# AT_SoM_Carrier_Board_V0_3r2.net
KiCad netlist of a schematic drawn in EAGLE
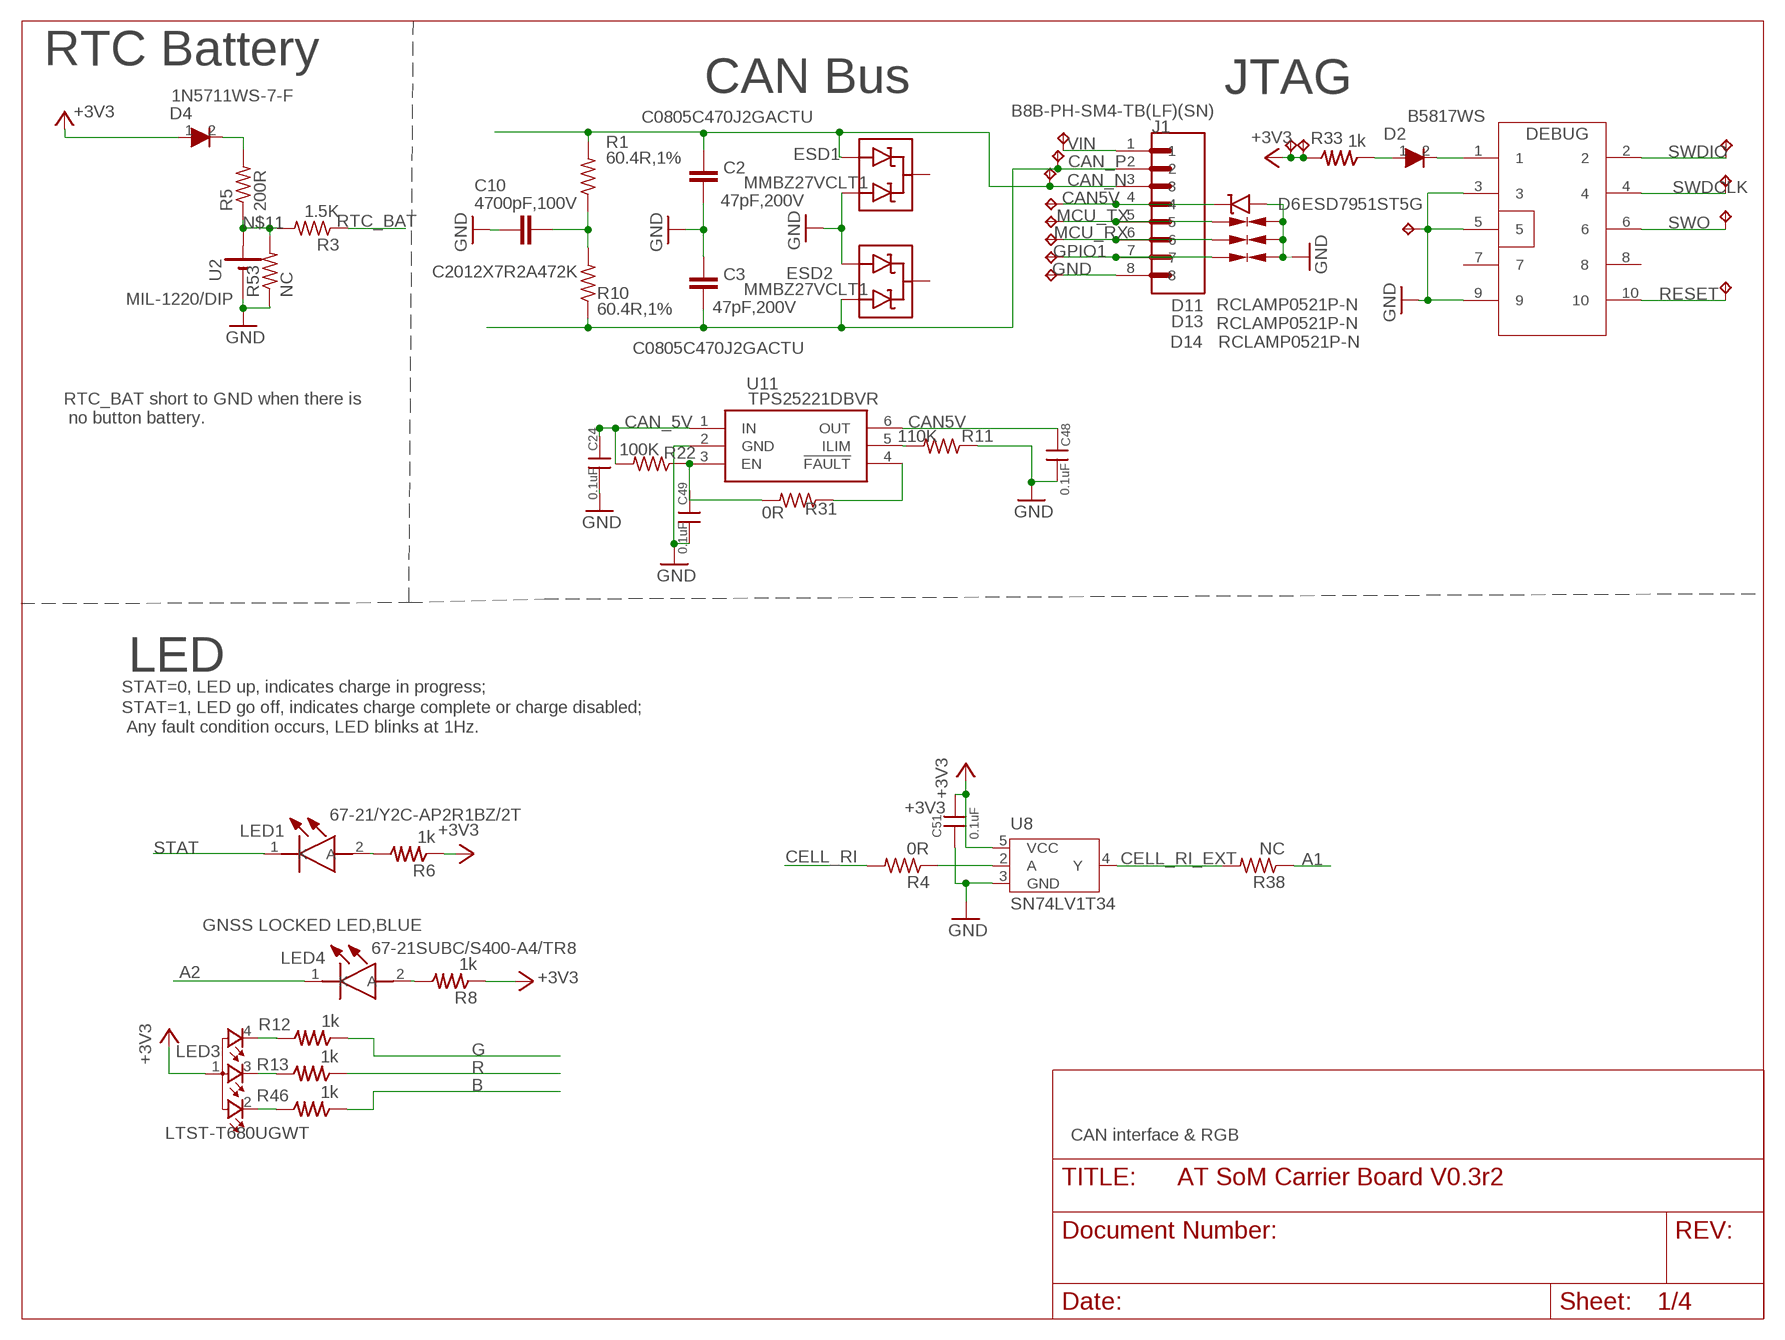
[diagram p0: schematic, sheet 1]
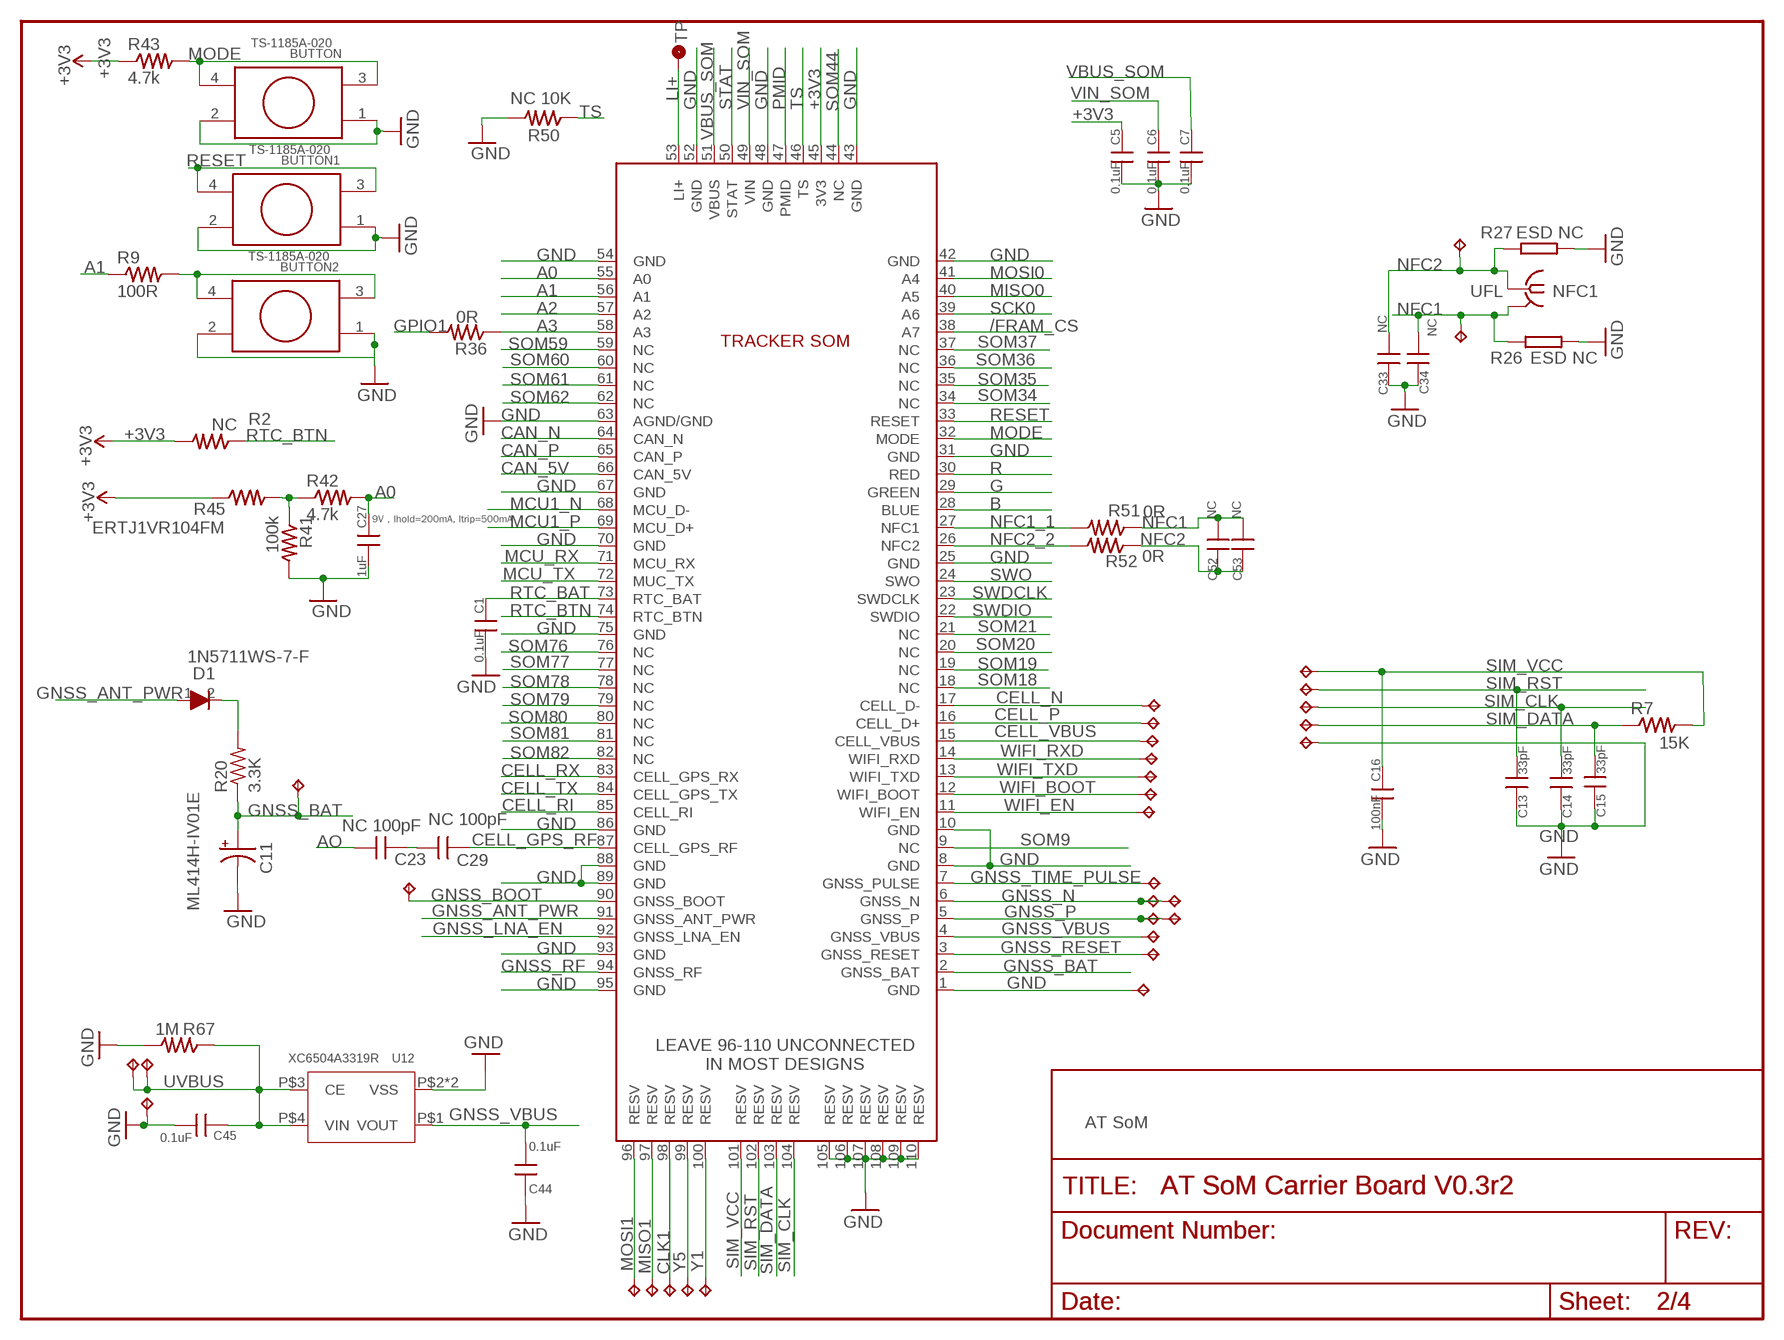
[diagram p1: schematic, sheet 2]
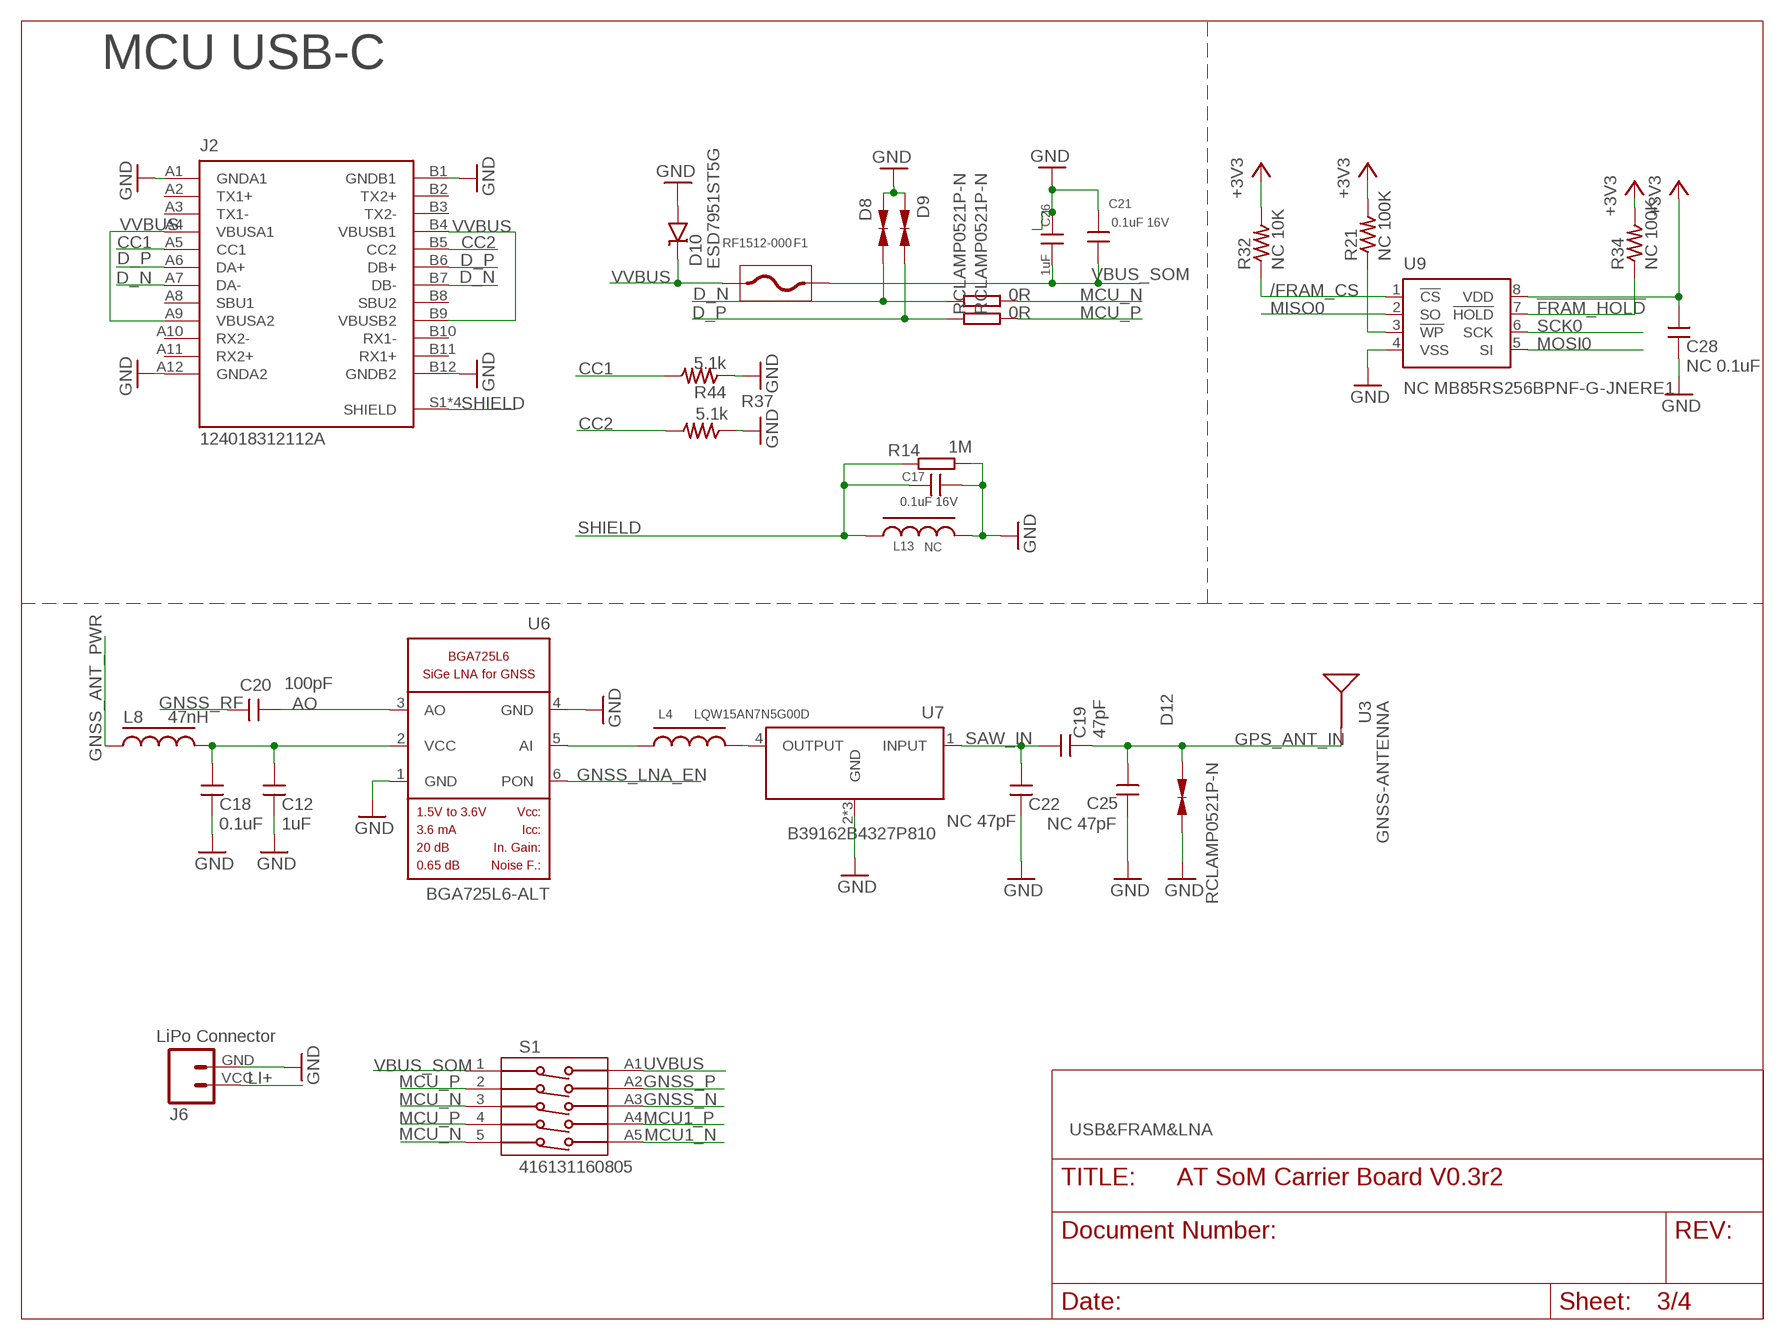
[diagram p2: schematic, sheet 3]
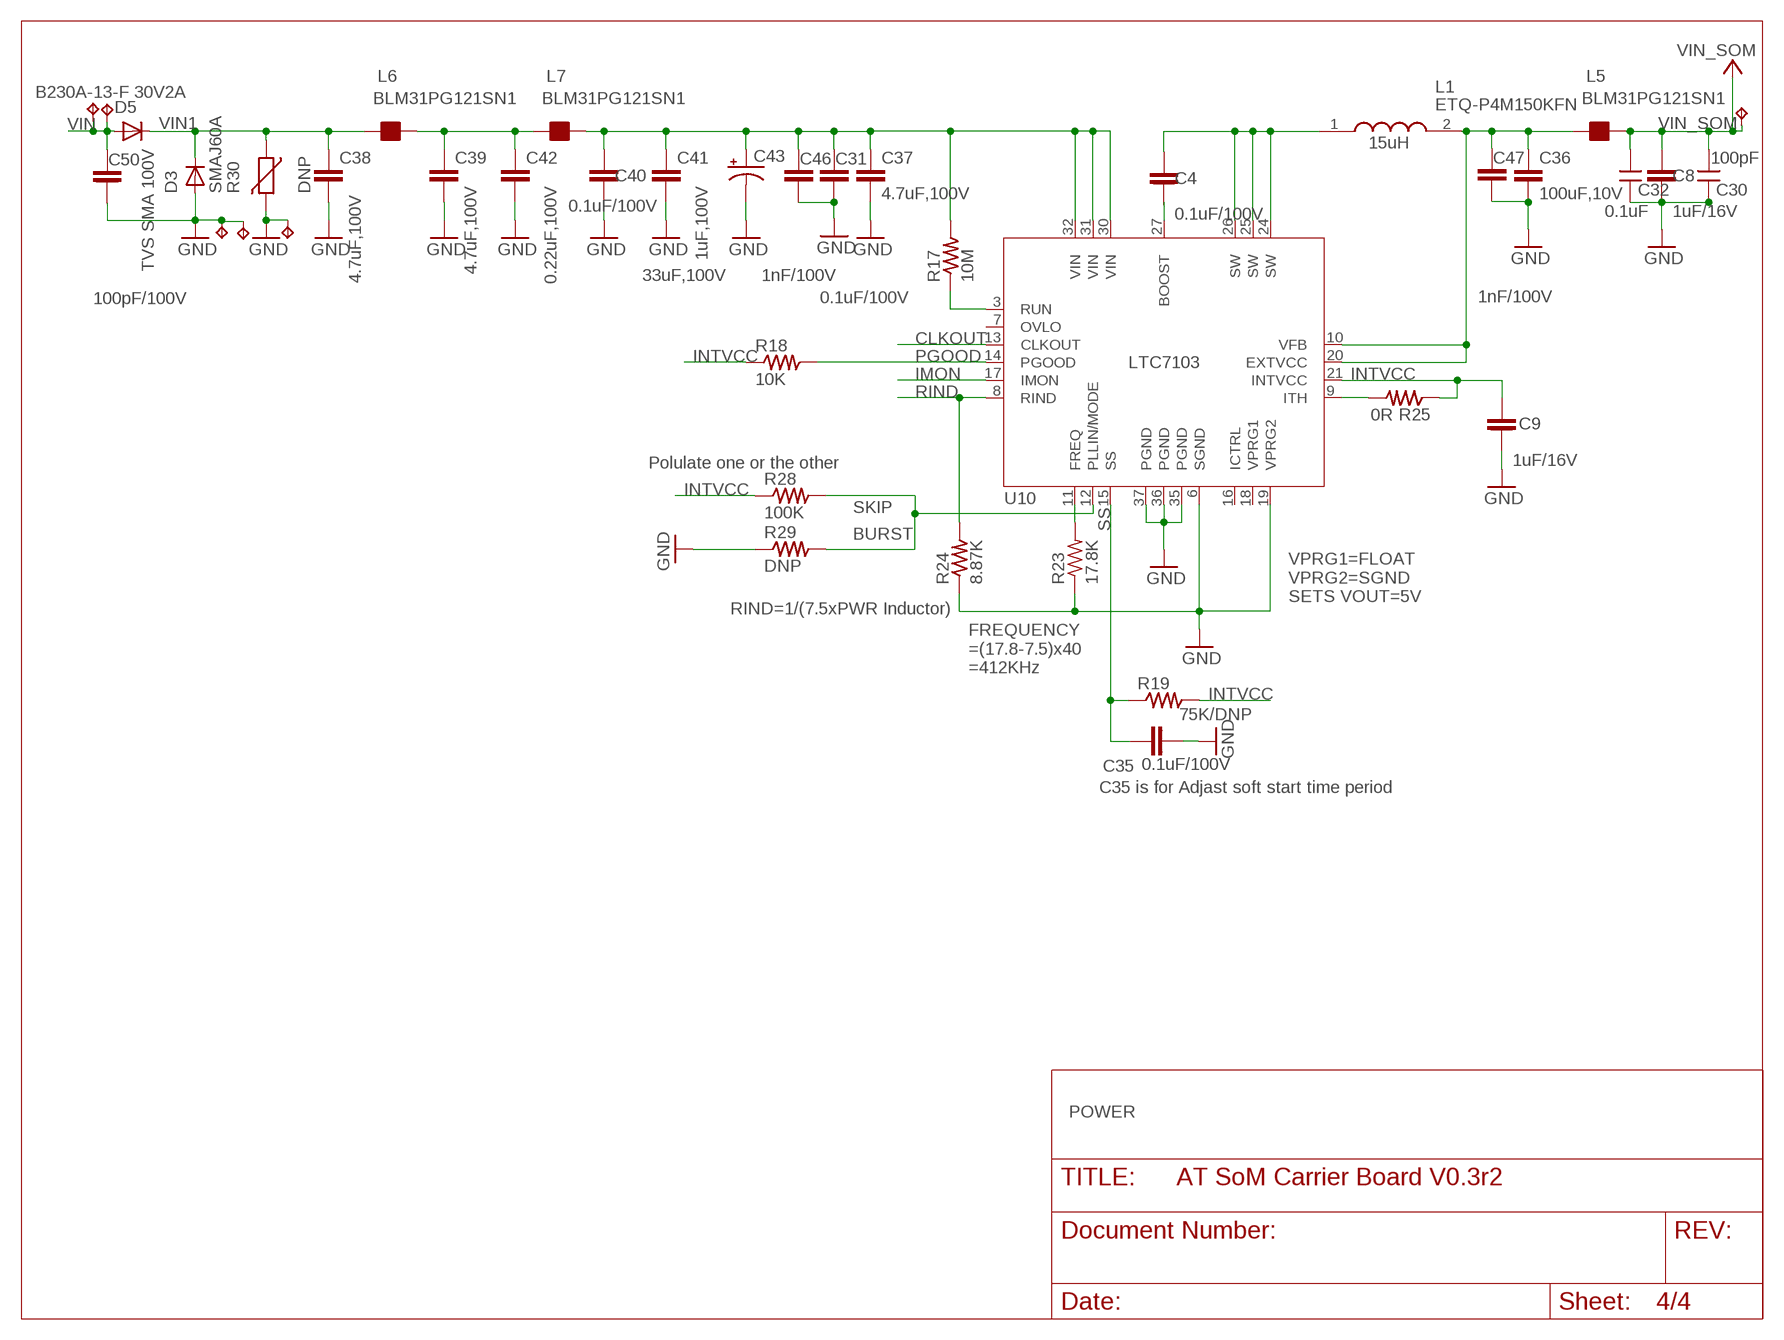
[diagram p3: schematic, sheet 4]

(export (version "E")
  (design (tool "Eeschema 10.0.6"))
  (components
    (comp (ref "C4")
      (value "0.1uF/100V")
      (footprint "eagle-import:C-0603A")
      (libsource (lib "eagle-import") (part "CAP0603A"))
    )
    (comp (ref "C8")
      (value "1uF/16V")
      (footprint "eagle-import:C-0402")
      (libsource (lib "eagle-import") (part "CAP0402"))
    )
    (comp (ref "C9")
      (value "1uF/16V")
      (footprint "eagle-import:C-0402")
      (libsource (lib "eagle-import") (part "CAP0402"))
    )
    (comp (ref "C30")
      (value "100pF")
      (footprint "eagle-import:C0402_P")
      (libsource (lib "eagle-import") (part "CAP_0402"))
    )
    (comp (ref "C31")
      (value "0.1uF/100V")
      (footprint "eagle-import:C-0603A")
      (libsource (lib "eagle-import") (part "CAP0603A"))
    )
    (comp (ref "C32")
      (value "0.1uF")
      (footprint "eagle-import:C0402_P")
      (libsource (lib "eagle-import") (part "CAP_0402"))
    )
    (comp (ref "C35")
      (value "0.1uF/100V")
      (footprint "eagle-import:C-0603A")
      (libsource (lib "eagle-import") (part "CAP0603A"))
    )
    (comp (ref "C36")
      (value "100uF,10V")
      (footprint "eagle-import:C1210")
      (libsource (lib "eagle-import") (part "C-EUC1210"))
    )
    (comp (ref "C37")
      (value "4.7uF,100V")
      (footprint "eagle-import:C1210")
      (libsource (lib "eagle-import") (part "C-EUC1210"))
    )
    (comp (ref "C38")
      (value "4.7uF,100V")
      (footprint "eagle-import:C1210")
      (libsource (lib "eagle-import") (part "C-EUC1210"))
    )
    (comp (ref "C39")
      (value "4.7uF,100V")
      (footprint "eagle-import:C1210")
      (libsource (lib "eagle-import") (part "C-EUC1210"))
    )
    (comp (ref "C40")
      (value "0.1uF/100V")
      (footprint "eagle-import:C-0603A")
      (libsource (lib "eagle-import") (part "CAP0603A"))
    )
    (comp (ref "C41")
      (value "1uF,100V")
      (footprint "eagle-import:C0805")
      (libsource (lib "eagle-import") (part "C-EUC0805"))
    )
    (comp (ref "C42")
      (value "0.22uF,100V")
      (footprint "eagle-import:C0805")
      (libsource (lib "eagle-import") (part "C-EUC0805"))
    )
    (comp (ref "C43")
      (value "33uF,100V")
      (footprint "eagle-import:NIC_10X10.5_CAP")
      (libsource (lib "eagle-import") (part "100UF-POLAR-10X10.5-63V-20%"))
    )
    (comp (ref "C46")
      (value "1nF/100V")
      (footprint "eagle-import:C-0603A")
      (libsource (lib "eagle-import") (part "CAP0603A"))
    )
    (comp (ref "C47")
      (value "1nF/100V")
      (footprint "eagle-import:C-0603A")
      (libsource (lib "eagle-import") (part "CAP0603A"))
    )
    (comp (ref "C50")
      (value "100pF/100V")
      (footprint "eagle-import:C-0603A")
      (libsource (lib "eagle-import") (part "CAP0603A"))
    )
    (comp (ref "D3")
      (value "SMAJ60A")
      (footprint "eagle-import:SMADIODE")
      (libsource (lib "eagle-import") (part "DIODESMA"))
    )
    (comp (ref "D5")
      (value "B230A-13-F 30V2A")
      (footprint "eagle-import:SMADIODE")
      (libsource (lib "eagle-import") (part "DIODESMA"))
    )
    (comp (ref "L1")
      (value "ETQ-P4M150KFN")
      (footprint "eagle-import:ETQP4M150KFN")
      (libsource (lib "eagle-import") (part "ETQ-P4M150KFN"))
    )
    (comp (ref "L5")
      (value "BLM31PG121SN1")
      (footprint "eagle-import:L1206")
      (libsource (lib "eagle-import") (part "FB_1206"))
    )
    (comp (ref "L6")
      (value "BLM31PG121SN1")
      (footprint "eagle-import:L1206")
      (libsource (lib "eagle-import") (part "FB_1206"))
    )
    (comp (ref "L7")
      (value "BLM31PG121SN1")
      (footprint "eagle-import:L1206")
      (libsource (lib "eagle-import") (part "FB_1206"))
    )
    (comp (ref "R17")
      (value "10M")
      (footprint "eagle-import:R-0402S")
      (libsource (lib "eagle-import") (part "RES0402S"))
    )
    (comp (ref "R18")
      (value "10K")
      (footprint "eagle-import:R-0402S")
      (libsource (lib "eagle-import") (part "RES0402S"))
    )
    (comp (ref "R19")
      (value "75K/DNP")
      (footprint "eagle-import:R-0402S")
      (libsource (lib "eagle-import") (part "RES0402S"))
    )
    (comp (ref "R23")
      (value "17.8K")
      (footprint "eagle-import:R0603_P")
      (libsource (lib "eagle-import") (part "RES_0603"))
    )
    (comp (ref "R24")
      (value "8.87K")
      (footprint "eagle-import:R-0402S")
      (libsource (lib "eagle-import") (part "RES0402S"))
    )
    (comp (ref "R25")
      (value "0R")
      (footprint "eagle-import:R-0402S")
      (libsource (lib "eagle-import") (part "RES0402S"))
    )
    (comp (ref "R28")
      (value "100K")
      (footprint "eagle-import:R-0402S")
      (libsource (lib "eagle-import") (part "RES0402S"))
    )
    (comp (ref "R29")
      (value "DNP")
      (footprint "eagle-import:R-0402S")
      (libsource (lib "eagle-import") (part "RES0402S"))
    )
    (comp (ref "R30")
      (value "DNP")
      (footprint "eagle-import:R-5")
      (libsource (lib "eagle-import") (part "VARISTOR-2,5"))
    )
    (comp (ref "TP10")
      (value "TPTP10R")
      (footprint "eagle-import:TP10R")
      (libsource (lib "eagle-import") (part "TPTP10R"))
    )
    (comp (ref "TP23")
      (value "TPTP10R")
      (footprint "eagle-import:TP10R")
      (libsource (lib "eagle-import") (part "TPTP10R"))
    )
    (comp (ref "TP24")
      (value "TPTP10R")
      (footprint "eagle-import:TP10R")
      (libsource (lib "eagle-import") (part "TPTP10R"))
    )
    (comp (ref "TP25")
      (value "TPTP10R")
      (footprint "eagle-import:TP10R")
      (libsource (lib "eagle-import") (part "TPTP10R"))
    )
    (comp (ref "TP26")
      (value "TPTP10R")
      (footprint "eagle-import:TP10R")
      (libsource (lib "eagle-import") (part "TPTP10R"))
    )
    (comp (ref "TP45")
      (value "TPTP10R")
      (footprint "eagle-import:TP10R")
      (libsource (lib "eagle-import") (part "TPTP10R"))
    )
    (comp (ref "U10")
      (value "LTC7103")
      (footprint "eagle-import:UHE36(26)QFN")
      (libsource (lib "eagle-import") (part "LTC7103"))
    )
    (comp (ref "BUTTON")
      (value "TS-1185A-020")
      (footprint "eagle-import:TS-1185A-020")
      (libsource (lib "eagle-import") (part "TS-1185A-020"))
    )
    (comp (ref "BUTTON1")
      (value "TS-1185A-020")
      (footprint "eagle-import:TS-1185A-020")
      (libsource (lib "eagle-import") (part "TS-1185A-020"))
    )
    (comp (ref "BUTTON2")
      (value "TS-1185A-020")
      (footprint "eagle-import:TS-1185A-020")
      (libsource (lib "eagle-import") (part "TS-1185A-020"))
    )
    (comp (ref "C1")
      (value "0.1uF")
      (footprint "eagle-import:C-0402")
      (libsource (lib "eagle-import") (part "RedBear_CAP0402"))
    )
    (comp (ref "C5")
      (value "0.1uF")
      (footprint "eagle-import:C-0402")
      (libsource (lib "eagle-import") (part "RedBear_CAP0402"))
    )
    (comp (ref "C6")
      (value "0.1uF")
      (footprint "eagle-import:C-0402")
      (libsource (lib "eagle-import") (part "RedBear_CAP0402"))
    )
    (comp (ref "C7")
      (value "0.1uF")
      (footprint "eagle-import:C-0402")
      (libsource (lib "eagle-import") (part "RedBear_CAP0402"))
    )
    (comp (ref "C11")
      (value "ML414H-IV01E")
      (footprint "eagle-import:ML414H")
      (libsource (lib "eagle-import") (part "ML414HIV01E"))
    )
    (comp (ref "C13")
      (value "33pF")
      (footprint "eagle-import:C-0402")
      (libsource (lib "eagle-import") (part "RedBear_CAP0402"))
    )
    (comp (ref "C14")
      (value "33pF")
      (footprint "eagle-import:C-0402")
      (libsource (lib "eagle-import") (part "RedBear_CAP0402"))
    )
    (comp (ref "C15")
      (value "33pF")
      (footprint "eagle-import:C-0402")
      (libsource (lib "eagle-import") (part "RedBear_CAP0402"))
    )
    (comp (ref "C16")
      (value "100nF")
      (footprint "eagle-import:C-0402")
      (libsource (lib "eagle-import") (part "RedBear_CAP0402"))
    )
    (comp (ref "C23")
      (value "NC 100pF")
      (footprint "eagle-import:C0402_P")
      (libsource (lib "eagle-import") (part "CAP_0402"))
    )
    (comp (ref "C27")
      (value "1uF")
      (footprint "eagle-import:C-0402")
      (libsource (lib "eagle-import") (part "RedBear_CAP0402"))
    )
    (comp (ref "C29")
      (value "NC 100pF")
      (footprint "eagle-import:C0402_P")
      (libsource (lib "eagle-import") (part "CAP_0402"))
    )
    (comp (ref "C33")
      (value "NC")
      (footprint "eagle-import:C-0402")
      (libsource (lib "eagle-import") (part "RedBear_CAP0402"))
    )
    (comp (ref "C34")
      (value "NC")
      (footprint "eagle-import:C-0402")
      (libsource (lib "eagle-import") (part "RedBear_CAP0402"))
    )
    (comp (ref "C44")
      (value "0.1uF")
      (footprint "eagle-import:C0201-S")
      (libsource (lib "eagle-import") (part "CAPC0201-S"))
    )
    (comp (ref "C45")
      (value "0.1uF")
      (footprint "eagle-import:C0201-S")
      (libsource (lib "eagle-import") (part "CAPC0201-S"))
    )
    (comp (ref "C52")
      (value "NC")
      (footprint "eagle-import:C-0402")
      (libsource (lib "eagle-import") (part "RedBear_CAP0402"))
    )
    (comp (ref "C53")
      (value "NC")
      (footprint "eagle-import:C-0402")
      (libsource (lib "eagle-import") (part "RedBear_CAP0402"))
    )
    (comp (ref "D1")
      (value "1N5711WS-7-F")
      (footprint "eagle-import:SOD-323")
      (libsource (lib "eagle-import") (part "DIODESOD323"))
    )
    (comp (ref "NFC1")
      (value "UFL")
      (footprint "eagle-import:IPEX-20279-001E")
      (libsource (lib "eagle-import") (part "IPEX-20279-001E"))
    )
    (comp (ref "R2")
      (value "NC")
      (footprint "eagle-import:R-0402S")
      (libsource (lib "eagle-import") (part "particle SZ_RES0402S"))
    )
    (comp (ref "R7")
      (value "15K")
      (footprint "eagle-import:R-0402S")
      (libsource (lib "eagle-import") (part "particle SZ_RES0402S"))
    )
    (comp (ref "R9")
      (value "100R")
      (footprint "eagle-import:R-0402S")
      (libsource (lib "eagle-import") (part "particle SZ_RES0402S"))
    )
    (comp (ref "R20")
      (value "3.3K")
      (footprint "eagle-import:R0603_P")
      (libsource (lib "eagle-import") (part "RES_0603"))
    )
    (comp (ref "R26")
      (value "ESD NC")
      (footprint "eagle-import:R-0402S")
      (libsource (lib "eagle-import") (part "RedBear_RES0402S"))
    )
    (comp (ref "R27")
      (value "ESD NC")
      (footprint "eagle-import:R-0402S")
      (libsource (lib "eagle-import") (part "RedBear_RES0402S"))
    )
    (comp (ref "R36")
      (value "0R")
      (footprint "eagle-import:R-0402S")
      (libsource (lib "eagle-import") (part "RES0402S"))
    )
    (comp (ref "R41")
      (value "100k")
      (footprint "eagle-import:R-0402S")
      (libsource (lib "eagle-import") (part "particle SZ_RES0402S"))
    )
    (comp (ref "R42")
      (value "4.7k")
      (footprint "eagle-import:R-0402S")
      (libsource (lib "eagle-import") (part "particle SZ_RES0402S"))
    )
    (comp (ref "R43")
      (value "4.7k")
      (footprint "eagle-import:R-0402S")
      (libsource (lib "eagle-import") (part "particle SZ_RES0402S"))
    )
    (comp (ref "R45")
      (value "ERTJ1VR104FM")
      (footprint "eagle-import:R0603")
      (libsource (lib "eagle-import") (part "RESR0603"))
    )
    (comp (ref "R50")
      (value "NC 10K")
      (footprint "eagle-import:R-0402S")
      (libsource (lib "eagle-import") (part "RES0402S"))
    )
    (comp (ref "R51")
      (value "0R")
      (footprint "eagle-import:R-0402S")
      (libsource (lib "eagle-import") (part "RES0402S"))
    )
    (comp (ref "R52")
      (value "0R")
      (footprint "eagle-import:R-0402S")
      (libsource (lib "eagle-import") (part "RES0402S"))
    )
    (comp (ref "R67")
      (value "1M")
      (footprint "eagle-import:R0201-S")
      (libsource (lib "eagle-import") (part "particle SZ_RESR0201-S"))
    )
    (comp (ref "TP1")
      (value "TPTP10R")
      (footprint "eagle-import:TP10R")
      (libsource (lib "eagle-import") (part "TPTP10R"))
    )
    (comp (ref "TP2")
      (value "TPTP10R")
      (footprint "eagle-import:TP10R")
      (libsource (lib "eagle-import") (part "TPTP10R"))
    )
    (comp (ref "TP3")
      (value "TPTP10R")
      (footprint "eagle-import:TP10R")
      (libsource (lib "eagle-import") (part "TPTP10R"))
    )
    (comp (ref "TP4")
      (value "TPTP10R")
      (footprint "eagle-import:TP10R")
      (libsource (lib "eagle-import") (part "TPTP10R"))
    )
    (comp (ref "TP5")
      (value "TPTP10R")
      (footprint "eagle-import:TP10R")
      (libsource (lib "eagle-import") (part "TPTP10R"))
    )
    (comp (ref "TP6")
      (value "TPTP10R")
      (footprint "eagle-import:TP10R")
      (libsource (lib "eagle-import") (part "TPTP10R"))
    )
    (comp (ref "TP7")
      (value "TPTP10R")
      (footprint "eagle-import:TP10R")
      (libsource (lib "eagle-import") (part "TPTP10R"))
    )
    (comp (ref "TP8")
      (value "TPTP10R")
      (footprint "eagle-import:TP10R")
      (libsource (lib "eagle-import") (part "TPTP10R"))
    )
    (comp (ref "TP9")
      (value "TPTP10R")
      (footprint "eagle-import:TP10R")
      (libsource (lib "eagle-import") (part "TPTP10R"))
    )
    (comp (ref "TP14")
      (value "TPTP10R")
      (footprint "eagle-import:TP10R")
      (libsource (lib "eagle-import") (part "TPTP10R"))
    )
    (comp (ref "TP17")
      (value "TPTP10R")
      (footprint "eagle-import:TP10R")
      (libsource (lib "eagle-import") (part "TPTP10R"))
    )
    (comp (ref "TP18")
      (value "TPTP10R")
      (footprint "eagle-import:TP10R")
      (libsource (lib "eagle-import") (part "TPTP10R"))
    )
    (comp (ref "TP19")
      (value "TPTP10R")
      (footprint "eagle-import:TP10R")
      (libsource (lib "eagle-import") (part "TPTP10R"))
    )
    (comp (ref "TP20")
      (value "TPTP10R")
      (footprint "eagle-import:TP10R")
      (libsource (lib "eagle-import") (part "TPTP10R"))
    )
    (comp (ref "TP27")
      (value "TPTP10R")
      (footprint "eagle-import:TP10R")
      (libsource (lib "eagle-import") (part "TPTP10R"))
    )
    (comp (ref "TP28")
      (value "TPTP10R")
      (footprint "eagle-import:TP10R")
      (libsource (lib "eagle-import") (part "TPTP10R"))
    )
    (comp (ref "TP29")
      (value "TPTP10R")
      (footprint "eagle-import:TP10R")
      (libsource (lib "eagle-import") (part "TPTP10R"))
    )
    (comp (ref "TP30")
      (value "TPTP10R")
      (footprint "eagle-import:TP10R")
      (libsource (lib "eagle-import") (part "TPTP10R"))
    )
    (comp (ref "TP31")
      (value "TPTP10R")
      (footprint "eagle-import:TP10R")
      (libsource (lib "eagle-import") (part "TPTP10R"))
    )
    (comp (ref "TP32")
      (value "TPTP10R")
      (footprint "eagle-import:TP10R")
      (libsource (lib "eagle-import") (part "TPTP10R"))
    )
    (comp (ref "TP33")
      (value "TPTP10R")
      (footprint "eagle-import:TP10R")
      (libsource (lib "eagle-import") (part "TPTP10R"))
    )
    (comp (ref "TP34")
      (value "TPTP10R")
      (footprint "eagle-import:TP10R")
      (libsource (lib "eagle-import") (part "TPTP10R"))
    )
    (comp (ref "TP35")
      (value "TPTP10R")
      (footprint "eagle-import:TP10R")
      (libsource (lib "eagle-import") (part "TPTP10R"))
    )
    (comp (ref "TP36")
      (value "TPTP10R")
      (footprint "eagle-import:TP10R")
      (libsource (lib "eagle-import") (part "TPTP10R"))
    )
    (comp (ref "TP37")
      (value "TPTP10R")
      (footprint "eagle-import:TP10R")
      (libsource (lib "eagle-import") (part "TPTP10R"))
    )
    (comp (ref "TP38")
      (value "TPTP10R")
      (footprint "eagle-import:TP10R")
      (libsource (lib "eagle-import") (part "TPTP10R"))
    )
    (comp (ref "TP39")
      (value "TPTP10R")
      (footprint "eagle-import:TP10R")
      (libsource (lib "eagle-import") (part "TPTP10R"))
    )
    (comp (ref "TP40")
      (value "TPTP10R")
      (footprint "eagle-import:TP10R")
      (libsource (lib "eagle-import") (part "TPTP10R"))
    )
    (comp (ref "TP41")
      (value "TPTP10R")
      (footprint "eagle-import:TP10R")
      (libsource (lib "eagle-import") (part "TPTP10R"))
    )
    (comp (ref "TP42")
      (value "TPTP10R")
      (footprint "eagle-import:TP10R")
      (libsource (lib "eagle-import") (part "TPTP10R"))
    )
    (comp (ref "U$1")
      (value "TP2")
      (footprint "eagle-import:TP70_BOT")
      (libsource (lib "eagle-import") (part "TP2"))
    )
    (comp (ref "U$9")
      (value "TPTP10R")
      (footprint "eagle-import:TP10R")
      (libsource (lib "eagle-import") (part "TPTP10R"))
    )
    (comp (ref "U$10")
      (value "TPTP10R")
      (footprint "eagle-import:TP10R")
      (libsource (lib "eagle-import") (part "TPTP10R"))
    )
    (comp (ref "U1")
      (value "TRACKER-SOM-3A")
      (footprint "eagle-import:TRACKER-SOM-3A")
      (libsource (lib "eagle-import") (part "TRACKER-SOM-3A"))
    )
    (comp (ref "U12")
      (value "XC6504A3319R")
      (footprint "eagle-import:USPQ-4B04")
      (libsource (lib "eagle-import") (part "XC6504USPQ"))
    )
    (comp (ref "C12")
      (value "1uF")
      (footprint "eagle-import:C0402_P")
      (libsource (lib "eagle-import") (part "CAP_0402"))
    )
    (comp (ref "C17")
      (value "0.1uF 16V")
      (footprint "eagle-import:PARTICLE-SZ_C-0402")
      (libsource (lib "eagle-import") (part "PARTICLE-SZ_CAP0402"))
    )
    (comp (ref "C18")
      (value "0.1uF")
      (footprint "eagle-import:C0402_P")
      (libsource (lib "eagle-import") (part "CAP_0402"))
    )
    (comp (ref "C19")
      (value "47pF")
      (footprint "eagle-import:C0402_P")
      (libsource (lib "eagle-import") (part "CAP_0402"))
    )
    (comp (ref "C20")
      (value "100pF")
      (footprint "eagle-import:C0402_P")
      (libsource (lib "eagle-import") (part "CAP_0402"))
    )
    (comp (ref "C21")
      (value "0.1uF 16V")
      (footprint "eagle-import:C-0402")
      (libsource (lib "eagle-import") (part "RedBear_CAP0402"))
    )
    (comp (ref "C22")
      (value "NC 47pF")
      (footprint "eagle-import:C0402_P")
      (libsource (lib "eagle-import") (part "CAP_0402"))
    )
    (comp (ref "C25")
      (value "NC 47pF")
      (footprint "eagle-import:C0402_P")
      (libsource (lib "eagle-import") (part "CAP_0402"))
    )
    (comp (ref "C26")
      (value "1uF")
      (footprint "eagle-import:C-0402")
      (libsource (lib "eagle-import") (part "RedBear_CAP0402"))
    )
    (comp (ref "C28")
      (value "NC 0.1uF")
      (footprint "eagle-import:C0402_P")
      (libsource (lib "eagle-import") (part "CAP_0402"))
    )
    (comp (ref "D8")
      (value "RCLAMP0521P-N")
      (footprint "eagle-import:C0402")
      (libsource (lib "eagle-import") (part "ESD"))
    )
    (comp (ref "D9")
      (value "RCLAMP0521P-N")
      (footprint "eagle-import:C0402")
      (libsource (lib "eagle-import") (part "ESD"))
    )
    (comp (ref "D10")
      (value "ESD7951ST5G")
      (footprint "eagle-import:0402-TVS-UNIDIR")
      (libsource (lib "eagle-import") (part "ESD-TVS-UNIDIR"))
    )
    (comp (ref "D12")
      (value "RCLAMP0521P-N")
      (footprint "eagle-import:C0402")
      (libsource (lib "eagle-import") (part "ESD"))
    )
    (comp (ref "F1")
      (value "RF1512-000")
      (footprint "eagle-import:R1206")
      (libsource (lib "eagle-import") (part "FUSEF1206"))
    )
    (comp (ref "J2")
      (value "124018312112A")
      (footprint "eagle-import:AMPHENOL_124018312112A")
      (fields (field (name "MF") "Amphenol ICC"))
      (libsource (lib "eagle-import") (part "124018312112A"))
    )
    (comp (ref "J6")
      (value "M024UCON-15767")
      (footprint "eagle-import:JST-2-SMD-VERT")
      (libsource (lib "eagle-import") (part "M024UCON-15767"))
    )
    (comp (ref "L4")
      (value "LQW15AN7N5G00D")
      (footprint "eagle-import:R-0402S")
      (libsource (lib "eagle-import") (part "L0402"))
    )
    (comp (ref "L8")
      (value "47nH")
      (footprint "eagle-import:R-0402S")
      (libsource (lib "eagle-import") (part "particle SZ_L0402"))
    )
    (comp (ref "L13")
      (value "NC")
      (footprint "eagle-import:R-0603A")
      (libsource (lib "eagle-import") (part "L"))
    )
    (comp (ref "R14")
      (value "1M")
      (footprint "eagle-import:REDBEAR_R0603")
      (libsource (lib "eagle-import") (part "REDBEAR_RESR0603"))
    )
    (comp (ref "R15")
      (value "0R")
      (footprint "eagle-import:R-0402S")
      (libsource (lib "eagle-import") (part "RedBear_RES0402S"))
    )
    (comp (ref "R16")
      (value "0R")
      (footprint "eagle-import:R-0402S")
      (libsource (lib "eagle-import") (part "RedBear_RES0402S"))
    )
    (comp (ref "R21")
      (value "NC 100K")
      (footprint "eagle-import:R-0402S")
      (libsource (lib "eagle-import") (part "RES0402S"))
    )
    (comp (ref "R32")
      (value "NC 10K")
      (footprint "eagle-import:R-0402S")
      (libsource (lib "eagle-import") (part "RES0402S"))
    )
    (comp (ref "R34")
      (value "NC 100K")
      (footprint "eagle-import:R-0402S")
      (libsource (lib "eagle-import") (part "RES0402S"))
    )
    (comp (ref "R37")
      (value "5.1k")
      (footprint "eagle-import:R-0402S")
      (libsource (lib "eagle-import") (part "RES0402S"))
    )
    (comp (ref "R44")
      (value "5.1k")
      (footprint "eagle-import:R-0402S")
      (libsource (lib "eagle-import") (part "RES0402S"))
    )
    (comp (ref "S1")
      (value "416131160805")
      (footprint "eagle-import:416131160805")
      (fields (field (name "MF") "Wurth Electronics"))
      (libsource (lib "eagle-import") (part "416131160805"))
    )
    (comp (ref "U3")
      (value "GNSS-ANTENNA")
      (footprint "eagle-import:PA035AZ0004")
      (libsource (lib "eagle-import") (part "GNSS-ANTENNA"))
    )
    (comp (ref "U6")
      (value "BGA725L6-ALT")
      (footprint "eagle-import:LNA-TSLP-6-2-ALT")
      (libsource (lib "eagle-import") (part "BGA725L6-ALT"))
    )
    (comp (ref "U7")
      (value "B39162B4327P810")
      (footprint "eagle-import:QCS5I")
      (libsource (lib "eagle-import") (part "FILTERS"))
    )
    (comp (ref "U9")
      (value "NC MB85RS256BPNF-G-JNERE1")
      (footprint "eagle-import:SO08")
      (libsource (lib "eagle-import") (part "MB85RS1MT"))
    )
    (comp (ref "C2")
      (value "47pF,200V")
      (footprint "eagle-import:C0805")
      (fields (field (name "PART_NUMBER") "C0805C470J2GACTU"))
      (libsource (lib "eagle-import") (part "C-EUC0805"))
    )
    (comp (ref "C3")
      (value "47pF,200V")
      (footprint "eagle-import:C0805")
      (fields (field (name "PART_NUMBER") "C0805C470J2GACTU"))
      (libsource (lib "eagle-import") (part "C-EUC0805"))
    )
    (comp (ref "C10")
      (value "4700pF,100V")
      (footprint "eagle-import:C0805")
      (fields (field (name "PART_NUMBER") "C2012X7R2A472K"))
      (libsource (lib "eagle-import") (part "C-EUC0805"))
    )
    (comp (ref "C24")
      (value "0.1uF")
      (footprint "eagle-import:C-0402")
      (libsource (lib "eagle-import") (part "RedBear_CAP0402"))
    )
    (comp (ref "C48")
      (value "0.1uF")
      (footprint "eagle-import:C-0402")
      (libsource (lib "eagle-import") (part "RedBear_CAP0402"))
    )
    (comp (ref "C49")
      (value "0.1uF")
      (footprint "eagle-import:C-0402")
      (libsource (lib "eagle-import") (part "RedBear_CAP0402"))
    )
    (comp (ref "C51")
      (value "0.1uF")
      (footprint "eagle-import:C-0402")
      (libsource (lib "eagle-import") (part "RedBear_CAP0402"))
    )
    (comp (ref "D2")
      (value "B5817WS")
      (footprint "eagle-import:SOD-323")
      (libsource (lib "eagle-import") (part "DIODESOD323"))
    )
    (comp (ref "D4")
      (value "1N5711WS-7-F")
      (footprint "eagle-import:SOD-323")
      (libsource (lib "eagle-import") (part "DIODESOD323"))
    )
    (comp (ref "D6")
      (value "ESD7951ST5G")
      (footprint "eagle-import:0402-TVS-UNIDIR")
      (libsource (lib "eagle-import") (part "ESD-TVS-UNIDIR"))
    )
    (comp (ref "D11")
      (value "RCLAMP0521P-N")
      (footprint "eagle-import:C0402")
      (libsource (lib "eagle-import") (part "ESD"))
    )
    (comp (ref "D13")
      (value "RCLAMP0521P-N")
      (footprint "eagle-import:C0402")
      (libsource (lib "eagle-import") (part "ESD"))
    )
    (comp (ref "D14")
      (value "RCLAMP0521P-N")
      (footprint "eagle-import:C0402")
      (libsource (lib "eagle-import") (part "ESD"))
    )
    (comp (ref "DEBUG")
      (value "CON5X2")
      (footprint "eagle-import:CON5X2_1.27")
      (libsource (lib "eagle-import") (part "CON5X2"))
    )
    (comp (ref "ESD1")
      (value "MMBZ27VCLT1")
      (footprint "eagle-import:SOT23-3")
      (libsource (lib "eagle-import") (part "MMBZ27VCLT1"))
    )
    (comp (ref "ESD2")
      (value "MMBZ27VCLT1")
      (footprint "eagle-import:SOT23-3")
      (libsource (lib "eagle-import") (part "MMBZ27VCLT1"))
    )
    (comp (ref "J1")
      (value "B8B-PH-SM4-TB(LF)(SN)")
      (footprint "eagle-import:JST_B8B-PH-SM4-TB(LF)(SN)")
      (libsource (lib "eagle-import") (part "B8B-PH-SM4-TB(LF)(SN)"))
    )
    (comp (ref "LED1")
      (value "67-21/Y2C-AP2R1BZ/2T")
      (footprint "eagle-import:LEDM3528X210N")
      (fields
        (field (name "MANUFACTURER_PART_NUMBER") "150141GS73113")
        (field (name "MOUSER_PART_NUMBER") "710-150141GS73113")
        (field (name "RS_PART_NUMBER") "1847238P")
      )
      (libsource (lib "eagle-import") (part "150141GS73113"))
    )
    (comp (ref "LED3")
      (value "LTST-T680UGWT")
      (footprint "eagle-import:150141M173100")
      (libsource (lib "eagle-import") (part "150141M173100"))
    )
    (comp (ref "LED4")
      (value "67-21SUBC/S400-A4/TR8")
      (footprint "eagle-import:LEDM3528X210N")
      (fields
        (field (name "MANUFACTURER_PART_NUMBER") "150141GS73113")
        (field (name "MOUSER_PART_NUMBER") "710-150141GS73113")
        (field (name "RS_PART_NUMBER") "1847238P")
      )
      (libsource (lib "eagle-import") (part "150141GS73113"))
    )
    (comp (ref "R1")
      (value "60.4R,1%")
      (footprint "eagle-import:R1206")
      (libsource (lib "eagle-import") (part "R-US_R1206"))
    )
    (comp (ref "R3")
      (value "1.5K")
      (footprint "eagle-import:R0402_B")
      (libsource (lib "eagle-import") (part "R-US_"))
    )
    (comp (ref "R4")
      (value "0R")
      (footprint "eagle-import:R0402_B")
      (libsource (lib "eagle-import") (part "R-US_"))
    )
    (comp (ref "R5")
      (value "200R")
      (footprint "eagle-import:R0402_B")
      (libsource (lib "eagle-import") (part "R-US_"))
    )
    (comp (ref "R6")
      (value "1k")
      (footprint "eagle-import:R-0402S")
      (libsource (lib "eagle-import") (part "particle SZ_RES0402S"))
    )
    (comp (ref "R8")
      (value "1k")
      (footprint "eagle-import:R-0402S")
      (libsource (lib "eagle-import") (part "particle SZ_RES0402S"))
    )
    (comp (ref "R10")
      (value "60.4R,1%")
      (footprint "eagle-import:R1206")
      (libsource (lib "eagle-import") (part "R-US_R1206"))
    )
    (comp (ref "R11")
      (value "110K")
      (footprint "eagle-import:R0402_B")
      (libsource (lib "eagle-import") (part "R-US_"))
    )
    (comp (ref "R12")
      (value "1k")
      (footprint "eagle-import:R-0402S")
      (libsource (lib "eagle-import") (part "particle SZ_RES0402S"))
    )
    (comp (ref "R13")
      (value "1k")
      (footprint "eagle-import:R-0402S")
      (libsource (lib "eagle-import") (part "particle SZ_RES0402S"))
    )
    (comp (ref "R22")
      (value "100K")
      (footprint "eagle-import:R0402_B")
      (libsource (lib "eagle-import") (part "R-US_"))
    )
    (comp (ref "R31")
      (value "0R")
      (footprint "eagle-import:R0402_B")
      (libsource (lib "eagle-import") (part "R-US_"))
    )
    (comp (ref "R33")
      (value "1k")
      (footprint "eagle-import:R-0402S")
      (libsource (lib "eagle-import") (part "particle SZ_RES0402S"))
    )
    (comp (ref "R38")
      (value "NC")
      (footprint "eagle-import:R0402_B")
      (libsource (lib "eagle-import") (part "R-US_"))
    )
    (comp (ref "R46")
      (value "1k")
      (footprint "eagle-import:R-0402S")
      (libsource (lib "eagle-import") (part "particle SZ_RES0402S"))
    )
    (comp (ref "R53")
      (value "NC")
      (footprint "eagle-import:R0402_B")
      (libsource (lib "eagle-import") (part "R-US_"))
    )
    (comp (ref "TP11")
      (value "TPTP10R")
      (footprint "eagle-import:TP10R")
      (libsource (lib "eagle-import") (part "TPTP10R"))
    )
    (comp (ref "TP12")
      (value "TPTP10R")
      (footprint "eagle-import:TP10R")
      (libsource (lib "eagle-import") (part "TPTP10R"))
    )
    (comp (ref "TP13")
      (value "TPTP10R")
      (footprint "eagle-import:TP10R")
      (libsource (lib "eagle-import") (part "TPTP10R"))
    )
    (comp (ref "TP15")
      (value "TPTP10R")
      (footprint "eagle-import:TP10R")
      (libsource (lib "eagle-import") (part "TPTP10R"))
    )
    (comp (ref "TP16")
      (value "TPTP10R")
      (footprint "eagle-import:TP10R")
      (libsource (lib "eagle-import") (part "TPTP10R"))
    )
    (comp (ref "TP21")
      (value "TPTP10R")
      (footprint "eagle-import:TP10R")
      (libsource (lib "eagle-import") (part "TPTP10R"))
    )
    (comp (ref "TP22")
      (value "TPTP10R")
      (footprint "eagle-import:TP10R")
      (libsource (lib "eagle-import") (part "TPTP10R"))
    )
    (comp (ref "TP43")
      (value "TPTP10R")
      (footprint "eagle-import:TP10R")
      (libsource (lib "eagle-import") (part "TPTP10R"))
    )
    (comp (ref "TP46")
      (value "TPTP10R")
      (footprint "eagle-import:TP10R")
      (libsource (lib "eagle-import") (part "TPTP10R"))
    )
    (comp (ref "TP47")
      (value "TPTP10R")
      (footprint "eagle-import:TP10R")
      (libsource (lib "eagle-import") (part "TPTP10R"))
    )
    (comp (ref "TP48")
      (value "TPTP10R")
      (footprint "eagle-import:TP10R")
      (libsource (lib "eagle-import") (part "TPTP10R"))
    )
    (comp (ref "TP49")
      (value "TPTP10R")
      (footprint "eagle-import:TP10R")
      (libsource (lib "eagle-import") (part "TPTP10R"))
    )
    (comp (ref "TP50")
      (value "TPTP10R")
      (footprint "eagle-import:TP10R")
      (libsource (lib "eagle-import") (part "TPTP10R"))
    )
    (comp (ref "TP51")
      (value "TPTP10R")
      (footprint "eagle-import:TP10R")
      (libsource (lib "eagle-import") (part "TPTP10R"))
    )
    (comp (ref "TP52")
      (value "TPTP10R")
      (footprint "eagle-import:TP10R")
      (libsource (lib "eagle-import") (part "TPTP10R"))
    )
    (comp (ref "U2")
      (value "MIL-1220/DIP")
      (footprint "eagle-import:BAT_ML-1220_DIP")
      (libsource (lib "eagle-import") (part "ML-1220/F1ANBAT_MIL-1220/DIP"))
    )
    (comp (ref "U8")
      (value "SN74LV1T34")
      (footprint "eagle-import:SC70-5")
      (libsource (lib "eagle-import") (part "SN74LV1T34"))
    )
    (comp (ref "U11")
      (value "TPS25221DBVR")
      (footprint "eagle-import:SOT95P280X145-6N")
      (fields (field (name "MOUSER_PART_NUMBER") "595-TPS25221DBVR"))
      (libsource (lib "eagle-import") (part "TPS25221DBVR"))
    )
  )
  (nets
    (net (code "1") (name "+3V3") (class "Default")
      (node (ref "C28") (pin "1") (pinfunction "1_1") (pintype "bidirectional"))
      (node (ref "C5") (pin "1") (pinfunction "1_1") (pintype "bidirectional"))
      (node (ref "C51") (pin "1") (pinfunction "1_1") (pintype "bidirectional"))
      (node (ref "D4") (pin "1") (pinfunction "P$1_1") (pintype "bidirectional"))
      (node (ref "LED3") (pin "1") (pinfunction "1_1") (pintype "passive"))
      (node (ref "R2") (pin "2") (pinfunction "2_2") (pintype "bidirectional"))
      (node (ref "R21") (pin "2") (pinfunction "2_2") (pintype "bidirectional"))
      (node (ref "R32") (pin "2") (pinfunction "2_2") (pintype "bidirectional"))
      (node (ref "R33") (pin "2") (pinfunction "2_2") (pintype "bidirectional"))
      (node (ref "R34") (pin "2") (pinfunction "2_2") (pintype "bidirectional"))
      (node (ref "R43") (pin "1") (pinfunction "1_1") (pintype "bidirectional"))
      (node (ref "R45") (pin "1") (pinfunction "1_1") (pintype "bidirectional"))
      (node (ref "R6") (pin "1") (pinfunction "1_1") (pintype "bidirectional"))
      (node (ref "R8") (pin "1") (pinfunction "1_1") (pintype "bidirectional"))
      (node (ref "TP16") (pin "TP") (pinfunction "TP_TP") (pintype "input"))
      (node (ref "TP21") (pin "TP") (pinfunction "TP_TP") (pintype "input"))
      (node (ref "U1") (pin "45") (pinfunction "3V3_45") (pintype "bidirectional"))
      (node (ref "U8") (pin "5") (pinfunction "VCC_5") (pintype "power_in"))
      (node (ref "U9") (pin "8") (pinfunction "VDD_8") (pintype "power_in"))
    )
    (net (code "2") (name "A0") (class "Default")
      (node (ref "C27") (pin "1") (pinfunction "1_1") (pintype "bidirectional"))
      (node (ref "R42") (pin "2") (pinfunction "2_2") (pintype "bidirectional"))
      (node (ref "U1") (pin "55") (pinfunction "A0_55") (pintype "bidirectional"))
    )
    (net (code "3") (name "A1") (class "Default")
      (node (ref "R38") (pin "1") (pinfunction "1_1") (pintype "passive"))
      (node (ref "R9") (pin "1") (pinfunction "1_1") (pintype "bidirectional"))
      (node (ref "U1") (pin "56") (pinfunction "A1_56") (pintype "bidirectional"))
    )
    (net (code "4") (name "A2") (class "Default")
      (node (ref "LED4") (pin "1") (pinfunction "K_1") (pintype "bidirectional"))
      (node (ref "U1") (pin "57") (pinfunction "A2_57") (pintype "bidirectional"))
    )
    (net (code "5") (name "A3") (class "Default")
      (node (ref "R36") (pin "1") (pinfunction "1_1") (pintype "bidirectional"))
      (node (ref "U1") (pin "58") (pinfunction "A3_58") (pintype "bidirectional"))
    )
    (net (code "6") (name "AO") (class "Default")
      (node (ref "C20") (pin "2") (pinfunction "2_2") (pintype "bidirectional"))
      (node (ref "C23") (pin "1") (pinfunction "1_1") (pintype "bidirectional"))
      (node (ref "U6") (pin "3") (pinfunction "AO_3") (pintype "output"))
    )
    (net (code "7") (name "B") (class "Default")
      (node (ref "R46") (pin "1") (pinfunction "1_1") (pintype "bidirectional"))
      (node (ref "U1") (pin "28") (pinfunction "BLUE_28") (pintype "bidirectional"))
    )
    (net (code "8") (name "CAN5V") (class "Default")
      (node (ref "C48") (pin "1") (pinfunction "1_1") (pintype "bidirectional"))
      (node (ref "D6") (pin "1") (pinfunction "1_1") (pintype "passive"))
      (node (ref "J1") (pin "4") (pinfunction "4_4") (pintype "passive"))
      (node (ref "TP48") (pin "TP") (pinfunction "TP_TP") (pintype "input"))
      (node (ref "U11") (pin "6") (pinfunction "OUT_6") (pintype "bidirectional"))
    )
    (net (code "9") (name "CAN_5V") (class "Default")
      (node (ref "C24") (pin "1") (pinfunction "1_1") (pintype "bidirectional"))
      (node (ref "R22") (pin "2") (pinfunction "2_2") (pintype "passive"))
      (node (ref "U1") (pin "66") (pinfunction "CAN_5V_66") (pintype "bidirectional"))
      (node (ref "U11") (pin "1") (pinfunction "IN_1") (pintype "bidirectional"))
    )
    (net (code "10") (name "CAN_N") (class "Default")
      (node (ref "C2") (pin "1") (pinfunction "1_1") (pintype "passive"))
      (node (ref "ESD1") (pin "2") (pinfunction "A2_2") (pintype "passive"))
      (node (ref "J1") (pin "3") (pinfunction "3_3") (pintype "passive"))
      (node (ref "R1") (pin "2") (pinfunction "2_2") (pintype "passive"))
      (node (ref "TP47") (pin "TP") (pinfunction "TP_TP") (pintype "input"))
      (node (ref "U1") (pin "64") (pinfunction "CAN_N_64") (pintype "bidirectional"))
    )
    (net (code "11") (name "CAN_P") (class "Default")
      (node (ref "C3") (pin "2") (pinfunction "2_2") (pintype "passive"))
      (node (ref "ESD2") (pin "1") (pinfunction "A1_1") (pintype "passive"))
      (node (ref "J1") (pin "2") (pinfunction "2_2") (pintype "passive"))
      (node (ref "R10") (pin "1") (pinfunction "1_1") (pintype "passive"))
      (node (ref "TP46") (pin "TP") (pinfunction "TP_TP") (pintype "input"))
      (node (ref "U1") (pin "65") (pinfunction "CAN_P_65") (pintype "bidirectional"))
    )
    (net (code "12") (name "CC1") (class "Default")
      (node (ref "J2") (pin "A5") (pinfunction "CC1_A5") (pintype "bidirectional"))
      (node (ref "R44") (pin "2") (pinfunction "2_2") (pintype "bidirectional"))
    )
    (net (code "13") (name "CC2") (class "Default")
      (node (ref "J2") (pin "B5") (pinfunction "CC2_B5") (pintype "bidirectional"))
      (node (ref "R37") (pin "2") (pinfunction "2_2") (pintype "bidirectional"))
    )
    (net (code "14") (name "CELL_GPS_RF") (class "Default")
      (node (ref "C29") (pin "2") (pinfunction "2_2") (pintype "bidirectional"))
      (node (ref "U1") (pin "87") (pinfunction "CELL_GPS_RF_87") (pintype "bidirectional"))
    )
    (net (code "15") (name "CELL_N") (class "Default")
      (node (ref "TP38") (pin "TP") (pinfunction "TP_TP") (pintype "input"))
      (node (ref "U1") (pin "17") (pinfunction "CELL_D-_17") (pintype "bidirectional"))
    )
    (net (code "16") (name "CELL_P") (class "Default")
      (node (ref "TP36") (pin "TP") (pinfunction "TP_TP") (pintype "input"))
      (node (ref "U1") (pin "16") (pinfunction "CELL_D+_16") (pintype "bidirectional"))
    )
    (net (code "17") (name "CELL_RI") (class "Default")
      (node (ref "R4") (pin "2") (pinfunction "2_2") (pintype "passive"))
      (node (ref "U1") (pin "85") (pinfunction "CELL_RI_85") (pintype "bidirectional"))
    )
    (net (code "18") (name "CELL_RI_EXT") (class "Default")
      (node (ref "R38") (pin "2") (pinfunction "2_2") (pintype "passive"))
      (node (ref "U8") (pin "4") (pinfunction "Y_4") (pintype "bidirectional"))
    )
    (net (code "19") (name "CELL_RX") (class "Default")
      (node (ref "U1") (pin "83") (pinfunction "CELL_GPS_RX_83") (pintype "bidirectional"))
    )
    (net (code "20") (name "CELL_TX") (class "Default")
      (node (ref "U1") (pin "84") (pinfunction "CELL_GPS_TX_84") (pintype "bidirectional"))
    )
    (net (code "21") (name "CELL_VBUS") (class "Default")
      (node (ref "TP35") (pin "TP") (pinfunction "TP_TP") (pintype "input"))
      (node (ref "U1") (pin "15") (pinfunction "CELL_VBUS_15") (pintype "bidirectional"))
    )
    (net (code "22") (name "CLK1") (class "Default")
      (node (ref "TP40") (pin "TP") (pinfunction "TP_TP") (pintype "input"))
      (node (ref "U1") (pin "98") (pinfunction "RESV_98") (pintype "bidirectional"))
    )
    (net (code "23") (name "CLKOUT") (class "Default")
      (node (ref "U10") (pin "13") (pinfunction "CLKOUT_13") (pintype "bidirectional"))
    )
    (net (code "24") (name "D_N") (class "Default")
      (node (ref "D8") (pin "2") (pinfunction "2_2") (pintype "bidirectional"))
      (node (ref "J2") (pin "A7") (pinfunction "DA-_A7") (pintype "bidirectional"))
      (node (ref "J2") (pin "B7") (pinfunction "DB-_B7") (pintype "bidirectional"))
      (node (ref "R15") (pin "1") (pinfunction "1_1") (pintype "bidirectional"))
    )
    (net (code "25") (name "D_P") (class "Default")
      (node (ref "D9") (pin "2") (pinfunction "2_2") (pintype "bidirectional"))
      (node (ref "J2") (pin "A6") (pinfunction "DA+_A6") (pintype "bidirectional"))
      (node (ref "J2") (pin "B6") (pinfunction "DB+_B6") (pintype "bidirectional"))
      (node (ref "R16") (pin "1") (pinfunction "1_1") (pintype "bidirectional"))
    )
    (net (code "26") (name "G") (class "Default")
      (node (ref "R12") (pin "1") (pinfunction "1_1") (pintype "bidirectional"))
      (node (ref "U1") (pin "29") (pinfunction "GREEN_29") (pintype "bidirectional"))
    )
    (net (code "27") (name "GND") (class "Default")
      (node (ref "BUTTON") (pin "1") (pinfunction "P$1_1") (pintype "bidirectional"))
      (node (ref "BUTTON") (pin "2") (pinfunction "P$2_2") (pintype "bidirectional"))
      (node (ref "BUTTON1") (pin "1") (pinfunction "P$1_1") (pintype "bidirectional"))
      (node (ref "BUTTON1") (pin "2") (pinfunction "P$2_2") (pintype "bidirectional"))
      (node (ref "BUTTON2") (pin "1") (pinfunction "P$1_1") (pintype "bidirectional"))
      (node (ref "BUTTON2") (pin "2") (pinfunction "P$2_2") (pintype "bidirectional"))
      (node (ref "C1") (pin "2") (pinfunction "2_2") (pintype "bidirectional"))
      (node (ref "C10") (pin "1") (pinfunction "1_1") (pintype "passive"))
      (node (ref "C11") (pin "-") (pinfunction "-_-") (pintype "passive"))
      (node (ref "C12") (pin "2") (pinfunction "2_2") (pintype "bidirectional"))
      (node (ref "C13") (pin "1") (pinfunction "1_1") (pintype "bidirectional"))
      (node (ref "C14") (pin "1") (pinfunction "1_1") (pintype "bidirectional"))
      (node (ref "C15") (pin "1") (pinfunction "1_1") (pintype "bidirectional"))
      (node (ref "C16") (pin "2") (pinfunction "2_2") (pintype "bidirectional"))
      (node (ref "C17") (pin "2") (pinfunction "2_2") (pintype "bidirectional"))
      (node (ref "C18") (pin "2") (pinfunction "2_2") (pintype "bidirectional"))
      (node (ref "C2") (pin "2") (pinfunction "2_2") (pintype "passive"))
      (node (ref "C21") (pin "2") (pinfunction "2_2") (pintype "bidirectional"))
      (node (ref "C22") (pin "2") (pinfunction "2_2") (pintype "bidirectional"))
      (node (ref "C24") (pin "2") (pinfunction "2_2") (pintype "bidirectional"))
      (node (ref "C25") (pin "1") (pinfunction "1_1") (pintype "bidirectional"))
      (node (ref "C26") (pin "1") (pinfunction "1_1") (pintype "bidirectional"))
      (node (ref "C27") (pin "2") (pinfunction "2_2") (pintype "bidirectional"))
      (node (ref "C28") (pin "2") (pinfunction "2_2") (pintype "bidirectional"))
      (node (ref "C3") (pin "1") (pinfunction "1_1") (pintype "passive"))
      (node (ref "C30") (pin "2") (pinfunction "2_2") (pintype "bidirectional"))
      (node (ref "C31") (pin "2") (pinfunction "2_2") (pintype "bidirectional"))
      (node (ref "C32") (pin "2") (pinfunction "2_2") (pintype "bidirectional"))
      (node (ref "C33") (pin "1") (pinfunction "1_1") (pintype "bidirectional"))
      (node (ref "C34") (pin "1") (pinfunction "1_1") (pintype "bidirectional"))
      (node (ref "C35") (pin "2") (pinfunction "2_2") (pintype "bidirectional"))
      (node (ref "C36") (pin "2") (pinfunction "2_2") (pintype "passive"))
      (node (ref "C37") (pin "2") (pinfunction "2_2") (pintype "passive"))
      (node (ref "C38") (pin "2") (pinfunction "2_2") (pintype "passive"))
      (node (ref "C39") (pin "2") (pinfunction "2_2") (pintype "passive"))
      (node (ref "C40") (pin "2") (pinfunction "2_2") (pintype "bidirectional"))
      (node (ref "C41") (pin "2") (pinfunction "2_2") (pintype "passive"))
      (node (ref "C42") (pin "2") (pinfunction "2_2") (pintype "passive"))
      (node (ref "C43") (pin "-") (pinfunction "-_-") (pintype "passive"))
      (node (ref "C44") (pin "1") (pinfunction "1_1") (pintype "bidirectional"))
      (node (ref "C45") (pin "2") (pinfunction "2_2") (pintype "bidirectional"))
      (node (ref "C46") (pin "2") (pinfunction "2_2") (pintype "bidirectional"))
      (node (ref "C47") (pin "2") (pinfunction "2_2") (pintype "bidirectional"))
      (node (ref "C48") (pin "2") (pinfunction "2_2") (pintype "bidirectional"))
      (node (ref "C49") (pin "2") (pinfunction "2_2") (pintype "bidirectional"))
      (node (ref "C5") (pin "2") (pinfunction "2_2") (pintype "bidirectional"))
      (node (ref "C50") (pin "2") (pinfunction "2_2") (pintype "bidirectional"))
      (node (ref "C51") (pin "2") (pinfunction "2_2") (pintype "bidirectional"))
      (node (ref "C6") (pin "2") (pinfunction "2_2") (pintype "bidirectional"))
      (node (ref "C7") (pin "2") (pinfunction "2_2") (pintype "bidirectional"))
      (node (ref "C8") (pin "2") (pinfunction "2_2") (pintype "bidirectional"))
      (node (ref "C9") (pin "2") (pinfunction "2_2") (pintype "bidirectional"))
      (node (ref "D10") (pin "2") (pinfunction "2_2") (pintype "passive"))
      (node (ref "D11") (pin "2") (pinfunction "2_2") (pintype "bidirectional"))
      (node (ref "D12") (pin "2") (pinfunction "2_2") (pintype "bidirectional"))
      (node (ref "D13") (pin "2") (pinfunction "2_2") (pintype "bidirectional"))
      (node (ref "D14") (pin "2") (pinfunction "2_2") (pintype "bidirectional"))
      (node (ref "D3") (pin "A") (pinfunction "A_A") (pintype "passive"))
      (node (ref "D6") (pin "2") (pinfunction "2_2") (pintype "passive"))
      (node (ref "D8") (pin "1") (pinfunction "1_1") (pintype "bidirectional"))
      (node (ref "D9") (pin "1") (pinfunction "1_1") (pintype "bidirectional"))
      (node (ref "DEBUG") (pin "3") (pinfunction "3_3") (pintype "bidirectional"))
      (node (ref "DEBUG") (pin "5") (pinfunction "5_5") (pintype "bidirectional"))
      (node (ref "DEBUG") (pin "9") (pinfunction "9_9") (pintype "bidirectional"))
      (node (ref "ESD1") (pin "1") (pinfunction "A1_1") (pintype "passive"))
      (node (ref "ESD2") (pin "2") (pinfunction "A2_2") (pintype "passive"))
      (node (ref "J1") (pin "8") (pinfunction "8_8") (pintype "passive"))
      (node (ref "J2") (pin "A1") (pinfunction "GNDA1_A1") (pintype "power_in"))
      (node (ref "J2") (pin "A12") (pinfunction "GNDA2_A12") (pintype "power_in"))
      (node (ref "J2") (pin "B1") (pinfunction "GNDB1_B1") (pintype "power_in"))
      (node (ref "J2") (pin "B12") (pinfunction "GNDB2_B12") (pintype "power_in"))
      (node (ref "J6") (pin "GND") (pinfunction "1_GND") (pintype "passive"))
      (node (ref "L13") (pin "2") (pinfunction "2_2") (pintype "bidirectional"))
      (node (ref "R11") (pin "1") (pinfunction "1_1") (pintype "passive"))
      (node (ref "R14") (pin "2") (pinfunction "2_2") (pintype "bidirectional"))
      (node (ref "R23") (pin "1") (pinfunction "1_1") (pintype "passive"))
      (node (ref "R24") (pin "1") (pinfunction "1_1") (pintype "bidirectional"))
      (node (ref "R26") (pin "2") (pinfunction "2_2") (pintype "bidirectional"))
      (node (ref "R27") (pin "1") (pinfunction "1_1") (pintype "bidirectional"))
      (node (ref "R29") (pin "1") (pinfunction "1_1") (pintype "bidirectional"))
      (node (ref "R30") (pin "2") (pinfunction "2_2") (pintype "passive"))
      (node (ref "R37") (pin "1") (pinfunction "1_1") (pintype "bidirectional"))
      (node (ref "R41") (pin "2") (pinfunction "2_2") (pintype "bidirectional"))
      (node (ref "R44") (pin "1") (pinfunction "1_1") (pintype "bidirectional"))
      (node (ref "R50") (pin "2") (pinfunction "2_2") (pintype "bidirectional"))
      (node (ref "R53") (pin "1") (pinfunction "1_1") (pintype "passive"))
      (node (ref "R67") (pin "2") (pinfunction "2_2") (pintype "bidirectional"))
      (node (ref "TP18") (pin "TP") (pinfunction "TP_TP") (pintype "input"))
      (node (ref "TP20") (pin "TP") (pinfunction "TP_TP") (pintype "input"))
      (node (ref "TP22") (pin "TP") (pinfunction "TP_TP") (pintype "input"))
      (node (ref "TP24") (pin "TP") (pinfunction "TP_TP") (pintype "input"))
      (node (ref "TP25") (pin "TP") (pinfunction "TP_TP") (pintype "input"))
      (node (ref "TP26") (pin "TP") (pinfunction "TP_TP") (pintype "input"))
      (node (ref "TP32") (pin "TP") (pinfunction "TP_TP") (pintype "input"))
      (node (ref "TP52") (pin "TP") (pinfunction "TP_TP") (pintype "input"))
      (node (ref "U1") (pin "1") (pinfunction "GND_1") (pintype "bidirectional"))
      (node (ref "U1") (pin "10") (pinfunction "GND_10") (pintype "bidirectional"))
      (node (ref "U1") (pin "105") (pinfunction "RESV_105") (pintype "bidirectional"))
      (node (ref "U1") (pin "106") (pinfunction "RESV_106") (pintype "bidirectional"))
      (node (ref "U1") (pin "107") (pinfunction "RESV_107") (pintype "bidirectional"))
      (node (ref "U1") (pin "108") (pinfunction "RESV_108") (pintype "bidirectional"))
      (node (ref "U1") (pin "109") (pinfunction "RESV_109") (pintype "bidirectional"))
      (node (ref "U1") (pin "110") (pinfunction "RESV_110") (pintype "bidirectional"))
      (node (ref "U1") (pin "25") (pinfunction "GND_25") (pintype "bidirectional"))
      (node (ref "U1") (pin "31") (pinfunction "GND_31") (pintype "bidirectional"))
      (node (ref "U1") (pin "42") (pinfunction "GND_42") (pintype "bidirectional"))
      (node (ref "U1") (pin "43") (pinfunction "GND_43") (pintype "bidirectional"))
      (node (ref "U1") (pin "48") (pinfunction "GND_48") (pintype "bidirectional"))
      (node (ref "U1") (pin "52") (pinfunction "GND_52") (pintype "bidirectional"))
      (node (ref "U1") (pin "54") (pinfunction "GND_54") (pintype "bidirectional"))
      (node (ref "U1") (pin "63") (pinfunction "AGND/GND_63") (pintype "bidirectional"))
      (node (ref "U1") (pin "67") (pinfunction "GND_67") (pintype "bidirectional"))
      (node (ref "U1") (pin "70") (pinfunction "GND_70") (pintype "bidirectional"))
      (node (ref "U1") (pin "75") (pinfunction "GND_75") (pintype "bidirectional"))
      (node (ref "U1") (pin "8") (pinfunction "GND_8") (pintype "bidirectional"))
      (node (ref "U1") (pin "86") (pinfunction "GND_86") (pintype "bidirectional"))
      (node (ref "U1") (pin "88") (pinfunction "GND_88") (pintype "bidirectional"))
      (node (ref "U1") (pin "89") (pinfunction "GND_89") (pintype "bidirectional"))
      (node (ref "U1") (pin "93") (pinfunction "GND_93") (pintype "bidirectional"))
      (node (ref "U1") (pin "95") (pinfunction "GND_95") (pintype "bidirectional"))
      (node (ref "U10") (pin "19") (pinfunction "VPRG2_19") (pintype "bidirectional"))
      (node (ref "U10") (pin "35") (pinfunction "PGND_35") (pintype "power_in"))
      (node (ref "U10") (pin "36") (pinfunction "PGND_36") (pintype "power_in"))
      (node (ref "U10") (pin "37") (pinfunction "PGND_37") (pintype "power_in"))
      (node (ref "U10") (pin "6") (pinfunction "SGND_6") (pintype "power_in"))
      (node (ref "U11") (pin "2") (pinfunction "GND_2") (pintype "bidirectional"))
      (node (ref "U12") (pin "P$2") (pinfunction "VSS_P$2") (pintype "bidirectional"))
      (node (ref "U12") (pin "P$5") (pinfunction "VSS_P$5") (pintype "bidirectional"))
      (node (ref "U2") (pin "1") (pinfunction "N_1") (pintype "power_in"))
      (node (ref "U6") (pin "1") (pinfunction "GND_1") (pintype "power_in"))
      (node (ref "U6") (pin "4") (pinfunction "GND_4") (pintype "power_in"))
      (node (ref "U7") (pin "2") (pinfunction "GND_2") (pintype "power_in"))
      (node (ref "U7") (pin "3") (pinfunction "GND_3") (pintype "power_in"))
      (node (ref "U7") (pin "5") (pinfunction "GND_5") (pintype "power_in"))
      (node (ref "U8") (pin "3") (pinfunction "GND_3") (pintype "power_in"))
      (node (ref "U9") (pin "4") (pinfunction "VSS_4") (pintype "power_in"))
    )
    (net (code "28") (name "GNSS_ANT_PWR") (class "Default")
      (node (ref "D1") (pin "1") (pinfunction "P$1_1") (pintype "bidirectional"))
      (node (ref "L8") (pin "1") (pinfunction "1_1") (pintype "bidirectional"))
      (node (ref "U1") (pin "91") (pinfunction "GNSS_ANT_PWR_91") (pintype "bidirectional"))
    )
    (net (code "29") (name "GNSS_BAT") (class "Default")
      (node (ref "C11") (pin "+") (pinfunction "+_+") (pintype "passive"))
      (node (ref "R20") (pin "1") (pinfunction "1_1") (pintype "passive"))
      (node (ref "TP9") (pin "TP") (pinfunction "TP_TP") (pintype "input"))
      (node (ref "U1") (pin "2") (pinfunction "GNSS_BAT_2") (pintype "bidirectional"))
    )
    (net (code "30") (name "GNSS_BOOT") (class "Default")
      (node (ref "TP6") (pin "TP") (pinfunction "TP_TP") (pintype "input"))
      (node (ref "U1") (pin "90") (pinfunction "GNSS_BOOT_90") (pintype "bidirectional"))
    )
    (net (code "31") (name "GNSS_LNA_EN") (class "Default")
      (node (ref "U1") (pin "92") (pinfunction "GNSS_LNA_EN_92") (pintype "bidirectional"))
      (node (ref "U6") (pin "6") (pinfunction "PON_6") (pintype "input"))
    )
    (net (code "32") (name "GNSS_N") (class "Default")
      (node (ref "S1") (pin "A3") (pinfunction "A3_A3") (pintype "passive"))
      (node (ref "TP14") (pin "TP") (pinfunction "TP_TP") (pintype "input"))
      (node (ref "TP34") (pin "TP") (pinfunction "TP_TP") (pintype "input"))
      (node (ref "U1") (pin "6") (pinfunction "GNSS_N_6") (pintype "bidirectional"))
    )
    (net (code "33") (name "GNSS_P") (class "Default")
      (node (ref "S1") (pin "A2") (pinfunction "A2_A2") (pintype "passive"))
      (node (ref "TP19") (pin "TP") (pinfunction "TP_TP") (pintype "input"))
      (node (ref "TP5") (pin "TP") (pinfunction "TP_TP") (pintype "input"))
      (node (ref "U1") (pin "5") (pinfunction "GNSS_P_5") (pintype "bidirectional"))
    )
    (net (code "34") (name "GNSS_RESET") (class "Default")
      (node (ref "TP8") (pin "TP") (pinfunction "TP_TP") (pintype "input"))
      (node (ref "U1") (pin "3") (pinfunction "GNSS_RESET_3") (pintype "bidirectional"))
    )
    (net (code "35") (name "GNSS_RF") (class "Default")
      (node (ref "C20") (pin "1") (pinfunction "1_1") (pintype "bidirectional"))
      (node (ref "U1") (pin "94") (pinfunction "GNSS_RF_94") (pintype "bidirectional"))
    )
    (net (code "36") (name "GNSS_TIME_PULSE") (class "Default")
      (node (ref "TP7") (pin "TP") (pinfunction "TP_TP") (pintype "input"))
      (node (ref "U1") (pin "7") (pinfunction "GNSS_PULSE_7") (pintype "bidirectional"))
    )
    (net (code "37") (name "GNSS_VBUS") (class "Default")
      (node (ref "C44") (pin "2") (pinfunction "2_2") (pintype "bidirectional"))
      (node (ref "TP30") (pin "TP") (pinfunction "TP_TP") (pintype "input"))
      (node (ref "U1") (pin "4") (pinfunction "GNSS_VBUS_4") (pintype "bidirectional"))
      (node (ref "U12") (pin "P$1") (pinfunction "VOUT_P$1") (pintype "bidirectional"))
    )
    (net (code "38") (name "GPIO1") (class "Default")
      (node (ref "D14") (pin "1") (pinfunction "1_1") (pintype "bidirectional"))
      (node (ref "J1") (pin "7") (pinfunction "7_7") (pintype "passive"))
      (node (ref "R36") (pin "2") (pinfunction "2_2") (pintype "bidirectional"))
      (node (ref "TP51") (pin "TP") (pinfunction "TP_TP") (pintype "input"))
    )
    (net (code "39") (name "GPS_ANT_IN") (class "Default")
      (node (ref "C19") (pin "2") (pinfunction "2_2") (pintype "bidirectional"))
      (node (ref "C25") (pin "2") (pinfunction "2_2") (pintype "bidirectional"))
      (node (ref "D12") (pin "1") (pinfunction "1_1") (pintype "bidirectional"))
      (node (ref "U3") (pin "P$1") (pinfunction "SIGNAL_P$1") (pintype "bidirectional"))
    )
    (net (code "40") (name "IMON") (class "Default")
      (node (ref "U10") (pin "17") (pinfunction "IMON_17") (pintype "bidirectional"))
    )
    (net (code "41") (name "INTVCC") (class "Default")
      (node (ref "C9") (pin "1") (pinfunction "1_1") (pintype "bidirectional"))
      (node (ref "R18") (pin "1") (pinfunction "1_1") (pintype "bidirectional"))
      (node (ref "R19") (pin "2") (pinfunction "2_2") (pintype "bidirectional"))
      (node (ref "R25") (pin "1") (pinfunction "1_1") (pintype "bidirectional"))
      (node (ref "R28") (pin "1") (pinfunction "1_1") (pintype "bidirectional"))
      (node (ref "U10") (pin "21") (pinfunction "INTVCC_21") (pintype "bidirectional"))
    )
    (net (code "42") (name "LI+") (class "Default")
      (node (ref "J6") (pin "VCC") (pinfunction "2_VCC") (pintype "passive"))
      (node (ref "U$1") (pin "P$1") (pinfunction "TP_P$1") (pintype "bidirectional"))
      (node (ref "U1") (pin "53") (pinfunction "LI+_53") (pintype "bidirectional"))
    )
    (net (code "43") (name "MCU1_N") (class "Default")
      (node (ref "S1") (pin "A5") (pinfunction "A5_A5") (pintype "passive"))
      (node (ref "U1") (pin "68") (pinfunction "MCU_D-_68") (pintype "bidirectional"))
    )
    (net (code "44") (name "MCU1_P") (class "Default")
      (node (ref "S1") (pin "A4") (pinfunction "A4_A4") (pintype "passive"))
      (node (ref "U1") (pin "69") (pinfunction "MCU_D+_69") (pintype "bidirectional"))
    )
    (net (code "45") (name "MCU_N") (class "Default")
      (node (ref "R15") (pin "2") (pinfunction "2_2") (pintype "bidirectional"))
      (node (ref "S1") (pin "3") (pinfunction "3_3") (pintype "passive"))
      (node (ref "S1") (pin "5") (pinfunction "5_5") (pintype "passive"))
    )
    (net (code "46") (name "MCU_P") (class "Default")
      (node (ref "R16") (pin "2") (pinfunction "2_2") (pintype "bidirectional"))
      (node (ref "S1") (pin "2") (pinfunction "2_2") (pintype "passive"))
      (node (ref "S1") (pin "4") (pinfunction "4_4") (pintype "passive"))
    )
    (net (code "47") (name "MCU_RX") (class "Default")
      (node (ref "D13") (pin "1") (pinfunction "1_1") (pintype "bidirectional"))
      (node (ref "J1") (pin "6") (pinfunction "6_6") (pintype "passive"))
      (node (ref "TP50") (pin "TP") (pinfunction "TP_TP") (pintype "input"))
      (node (ref "U1") (pin "71") (pinfunction "MCU_RX_71") (pintype "bidirectional"))
    )
    (net (code "48") (name "MCU_TX") (class "Default")
      (node (ref "D11") (pin "1") (pinfunction "1_1") (pintype "bidirectional"))
      (node (ref "J1") (pin "5") (pinfunction "5_5") (pintype "passive"))
      (node (ref "TP49") (pin "TP") (pinfunction "TP_TP") (pintype "input"))
      (node (ref "U1") (pin "72") (pinfunction "MUC_TX_72") (pintype "bidirectional"))
    )
    (net (code "49") (name "MISO0") (class "Default")
      (node (ref "U1") (pin "40") (pinfunction "A5_40") (pintype "bidirectional"))
      (node (ref "U9") (pin "2") (pinfunction "SO_2") (pintype "output"))
    )
    (net (code "50") (name "MISO1") (class "Default")
      (node (ref "TP39") (pin "TP") (pinfunction "TP_TP") (pintype "input"))
      (node (ref "U1") (pin "97") (pinfunction "RESV_97") (pintype "bidirectional"))
    )
    (net (code "51") (name "MODE") (class "Default")
      (node (ref "BUTTON") (pin "3") (pinfunction "P$3_3") (pintype "bidirectional"))
      (node (ref "BUTTON") (pin "4") (pinfunction "P$4_4") (pintype "bidirectional"))
      (node (ref "R43") (pin "2") (pinfunction "2_2") (pintype "bidirectional"))
      (node (ref "U1") (pin "32") (pinfunction "MODE_32") (pintype "bidirectional"))
    )
    (net (code "52") (name "MOSI0") (class "Default")
      (node (ref "U1") (pin "41") (pinfunction "A4_41") (pintype "bidirectional"))
      (node (ref "U9") (pin "5") (pinfunction "SI_5") (pintype "output"))
    )
    (net (code "53") (name "MOSI1") (class "Default")
      (node (ref "TP37") (pin "TP") (pinfunction "TP_TP") (pintype "input"))
      (node (ref "U1") (pin "96") (pinfunction "RESV_96") (pintype "bidirectional"))
    )
    (net (code "54") (name "N$11") (class "Default")
      (node (ref "R3") (pin "2") (pinfunction "2_2") (pintype "passive"))
      (node (ref "R5") (pin "1") (pinfunction "1_1") (pintype "passive"))
      (node (ref "R53") (pin "2") (pinfunction "2_2") (pintype "passive"))
      (node (ref "U2") (pin "2") (pinfunction "P_2") (pintype "power_in"))
    )
    (net (code "55") (name "NFC1") (class "Default")
      (node (ref "C34") (pin "2") (pinfunction "2_2") (pintype "bidirectional"))
      (node (ref "C52") (pin "2") (pinfunction "2_2") (pintype "bidirectional"))
      (node (ref "C53") (pin "2") (pinfunction "2_2") (pintype "bidirectional"))
      (node (ref "NFC1") (pin "2@1") (pinfunction "GND_2@1") (pintype "passive"))
      (node (ref "NFC1") (pin "2@2") (pinfunction "GND_2@2") (pintype "passive"))
      (node (ref "R26") (pin "1") (pinfunction "1_1") (pintype "bidirectional"))
      (node (ref "R51") (pin "1") (pinfunction "1_1") (pintype "bidirectional"))
      (node (ref "U$10") (pin "TP") (pinfunction "TP_TP") (pintype "input"))
    )
    (net (code "56") (name "NFC1_1") (class "Default")
      (node (ref "R51") (pin "2") (pinfunction "2_2") (pintype "bidirectional"))
      (node (ref "U1") (pin "27") (pinfunction "NFC1_27") (pintype "bidirectional"))
    )
    (net (code "57") (name "NFC2") (class "Default")
      (node (ref "C33") (pin "2") (pinfunction "2_2") (pintype "bidirectional"))
      (node (ref "C52") (pin "1") (pinfunction "1_1") (pintype "bidirectional"))
      (node (ref "C53") (pin "1") (pinfunction "1_1") (pintype "bidirectional"))
      (node (ref "NFC1") (pin "1") (pinfunction "1_1") (pintype "passive"))
      (node (ref "R27") (pin "2") (pinfunction "2_2") (pintype "bidirectional"))
      (node (ref "R52") (pin "1") (pinfunction "1_1") (pintype "bidirectional"))
      (node (ref "U$9") (pin "TP") (pinfunction "TP_TP") (pintype "input"))
    )
    (net (code "58") (name "NFC2_2") (class "Default")
      (node (ref "R52") (pin "2") (pinfunction "2_2") (pintype "bidirectional"))
      (node (ref "U1") (pin "26") (pinfunction "NFC2_26") (pintype "bidirectional"))
    )
    (net (code "59") (name "Net-(BUTTON2-P$3)") (class "Default")
      (node (ref "BUTTON2") (pin "3") (pinfunction "P$3_3") (pintype "bidirectional"))
      (node (ref "BUTTON2") (pin "4") (pinfunction "P$4_4") (pintype "bidirectional"))
      (node (ref "R9") (pin "2") (pinfunction "2_2") (pintype "bidirectional"))
    )
    (net (code "60") (name "Net-(C4-Pad1)") (class "Default")
      (node (ref "C4") (pin "1") (pinfunction "1_1") (pintype "bidirectional"))
      (node (ref "L1") (pin "1") (pinfunction "1_1") (pintype "bidirectional"))
      (node (ref "U10") (pin "24") (pinfunction "SW_24") (pintype "power_in"))
      (node (ref "U10") (pin "25") (pinfunction "SW_25") (pintype "power_in"))
      (node (ref "U10") (pin "26") (pinfunction "SW_26") (pintype "power_in"))
    )
    (net (code "61") (name "Net-(C10-Pad2)") (class "Default")
      (node (ref "C10") (pin "2") (pinfunction "2_2") (pintype "passive"))
      (node (ref "R1") (pin "1") (pinfunction "1_1") (pintype "passive"))
      (node (ref "R10") (pin "2") (pinfunction "2_2") (pintype "passive"))
    )
    (net (code "62") (name "Net-(C23-Pad2)") (class "Default")
      (node (ref "C23") (pin "2") (pinfunction "2_2") (pintype "bidirectional"))
      (node (ref "C29") (pin "1") (pinfunction "1_1") (pintype "bidirectional"))
    )
    (net (code "63") (name "Net-(C31-Pad1)") (class "Default")
      (node (ref "C31") (pin "1") (pinfunction "1_1") (pintype "bidirectional"))
      (node (ref "C37") (pin "1") (pinfunction "1_1") (pintype "passive"))
      (node (ref "C40") (pin "1") (pinfunction "1_1") (pintype "bidirectional"))
      (node (ref "C41") (pin "1") (pinfunction "1_1") (pintype "passive"))
      (node (ref "C43") (pin "+") (pinfunction "+_+") (pintype "passive"))
      (node (ref "C46") (pin "1") (pinfunction "1_1") (pintype "bidirectional"))
      (node (ref "L7") (pin "2") (pinfunction "2_2") (pintype "passive"))
      (node (ref "R17") (pin "2") (pinfunction "2_2") (pintype "bidirectional"))
      (node (ref "U10") (pin "30") (pinfunction "VIN_30") (pintype "power_in"))
      (node (ref "U10") (pin "31") (pinfunction "VIN_31") (pintype "power_in"))
      (node (ref "U10") (pin "32") (pinfunction "VIN_32") (pintype "power_in"))
    )
    (net (code "64") (name "Net-(C39-Pad1)") (class "Default")
      (node (ref "C39") (pin "1") (pinfunction "1_1") (pintype "passive"))
      (node (ref "C42") (pin "1") (pinfunction "1_1") (pintype "passive"))
      (node (ref "L6") (pin "2") (pinfunction "2_2") (pintype "passive"))
      (node (ref "L7") (pin "1") (pinfunction "1_1") (pintype "passive"))
    )
    (net (code "65") (name "Net-(D1-P$2)") (class "Default")
      (node (ref "D1") (pin "2") (pinfunction "P$2_2") (pintype "bidirectional"))
      (node (ref "R20") (pin "2") (pinfunction "2_2") (pintype "passive"))
    )
    (net (code "66") (name "Net-(D2-P$1)") (class "Default")
      (node (ref "D2") (pin "1") (pinfunction "P$1_1") (pintype "bidirectional"))
      (node (ref "R33") (pin "1") (pinfunction "1_1") (pintype "bidirectional"))
    )
    (net (code "67") (name "Net-(D2-P$2)") (class "Default")
      (node (ref "D2") (pin "2") (pinfunction "P$2_2") (pintype "bidirectional"))
      (node (ref "DEBUG") (pin "1") (pinfunction "1_1") (pintype "bidirectional"))
    )
    (net (code "68") (name "Net-(D4-P$2)") (class "Default")
      (node (ref "D4") (pin "2") (pinfunction "P$2_2") (pintype "bidirectional"))
      (node (ref "R5") (pin "2") (pinfunction "2_2") (pintype "passive"))
    )
    (net (code "69") (name "Net-(LED1-A)") (class "Default")
      (node (ref "LED1") (pin "2") (pinfunction "A_2") (pintype "bidirectional"))
      (node (ref "R6") (pin "2") (pinfunction "2_2") (pintype "bidirectional"))
    )
    (net (code "70") (name "Net-(LED3-Pad2)") (class "Default")
      (node (ref "LED3") (pin "2") (pinfunction "2_2") (pintype "passive"))
      (node (ref "R46") (pin "2") (pinfunction "2_2") (pintype "bidirectional"))
    )
    (net (code "71") (name "Net-(LED3-Pad3)") (class "Default")
      (node (ref "LED3") (pin "3") (pinfunction "3_3") (pintype "passive"))
      (node (ref "R13") (pin "2") (pinfunction "2_2") (pintype "bidirectional"))
    )
    (net (code "72") (name "Net-(LED3-Pad4)") (class "Default")
      (node (ref "LED3") (pin "4") (pinfunction "4_4") (pintype "passive"))
      (node (ref "R12") (pin "2") (pinfunction "2_2") (pintype "bidirectional"))
    )
    (net (code "73") (name "Net-(LED4-A)") (class "Default")
      (node (ref "LED4") (pin "2") (pinfunction "A_2") (pintype "bidirectional"))
      (node (ref "R8") (pin "2") (pinfunction "2_2") (pintype "bidirectional"))
    )
    (net (code "74") (name "Net-(R41-Pad1)") (class "Default")
      (node (ref "R41") (pin "1") (pinfunction "1_1") (pintype "bidirectional"))
      (node (ref "R42") (pin "1") (pinfunction "1_1") (pintype "bidirectional"))
      (node (ref "R45") (pin "2") (pinfunction "2_2") (pintype "bidirectional"))
    )
    (net (code "75") (name "Net-(U6-AI)") (class "Default")
      (node (ref "L4") (pin "1") (pinfunction "1_1") (pintype "bidirectional"))
      (node (ref "U6") (pin "5") (pinfunction "AI_5") (pintype "input"))
    )
    (net (code "76") (name "Net-(U6-VCC)") (class "Default")
      (node (ref "C12") (pin "1") (pinfunction "1_1") (pintype "bidirectional"))
      (node (ref "C18") (pin "1") (pinfunction "1_1") (pintype "bidirectional"))
      (node (ref "L8") (pin "2") (pinfunction "2_2") (pintype "bidirectional"))
      (node (ref "U6") (pin "2") (pinfunction "VCC_2") (pintype "power_in"))
    )
    (net (code "77") (name "Net-(U7-OUTPUT)") (class "Default")
      (node (ref "L4") (pin "2") (pinfunction "2_2") (pintype "bidirectional"))
      (node (ref "U7") (pin "4") (pinfunction "OUTPUT_4") (pintype "bidirectional"))
    )
    (net (code "78") (name "Net-(U8-A)") (class "Default")
      (node (ref "R4") (pin "1") (pinfunction "1_1") (pintype "passive"))
      (node (ref "U8") (pin "2") (pinfunction "A_2") (pintype "bidirectional"))
    )
    (net (code "79") (name "Net-(U9-~{WP})") (class "Default")
      (node (ref "R21") (pin "1") (pinfunction "1_1") (pintype "bidirectional"))
      (node (ref "U9") (pin "3") (pinfunction "~{WP}_3") (pintype "input"))
    )
    (net (code "80") (name "Net-(U10-BOOST)") (class "Default")
      (node (ref "C4") (pin "2") (pinfunction "2_2") (pintype "bidirectional"))
      (node (ref "U10") (pin "27") (pinfunction "BOOST_27") (pintype "bidirectional"))
    )
    (net (code "81") (name "Net-(U10-EXTVCC)") (class "Default")
      (node (ref "C36") (pin "1") (pinfunction "1_1") (pintype "passive"))
      (node (ref "C47") (pin "1") (pinfunction "1_1") (pintype "bidirectional"))
      (node (ref "L1") (pin "2") (pinfunction "2_2") (pintype "bidirectional"))
      (node (ref "L5") (pin "1") (pinfunction "1_1") (pintype "passive"))
      (node (ref "U10") (pin "10") (pinfunction "VFB_10") (pintype "bidirectional"))
      (node (ref "U10") (pin "20") (pinfunction "EXTVCC_20") (pintype "bidirectional"))
    )
    (net (code "82") (name "Net-(U10-FREQ)") (class "Default")
      (node (ref "R23") (pin "2") (pinfunction "2_2") (pintype "passive"))
      (node (ref "U10") (pin "11") (pinfunction "FREQ_11") (pintype "bidirectional"))
    )
    (net (code "83") (name "Net-(U10-ITH)") (class "Default")
      (node (ref "R25") (pin "2") (pinfunction "2_2") (pintype "bidirectional"))
      (node (ref "U10") (pin "9") (pinfunction "ITH_9") (pintype "bidirectional"))
    )
    (net (code "84") (name "Net-(U10-PLLIN{slash}MODE)") (class "Default")
      (node (ref "R28") (pin "2") (pinfunction "2_2") (pintype "bidirectional"))
      (node (ref "R29") (pin "2") (pinfunction "2_2") (pintype "bidirectional"))
      (node (ref "U10") (pin "12") (pinfunction "PLLIN/MODE_12") (pintype "bidirectional"))
    )
    (net (code "85") (name "Net-(U10-RUN)") (class "Default")
      (node (ref "R17") (pin "1") (pinfunction "1_1") (pintype "bidirectional"))
      (node (ref "U10") (pin "3") (pinfunction "RUN_3") (pintype "bidirectional"))
    )
    (net (code "86") (name "Net-(U11-EN)") (class "Default")
      (node (ref "C49") (pin "1") (pinfunction "1_1") (pintype "bidirectional"))
      (node (ref "R22") (pin "1") (pinfunction "1_1") (pintype "passive"))
      (node (ref "R31") (pin "2") (pinfunction "2_2") (pintype "passive"))
      (node (ref "U11") (pin "3") (pinfunction "EN_3") (pintype "bidirectional"))
    )
    (net (code "87") (name "Net-(U11-ILIM)") (class "Default")
      (node (ref "R11") (pin "2") (pinfunction "2_2") (pintype "passive"))
      (node (ref "U11") (pin "5") (pinfunction "ILIM_5") (pintype "bidirectional"))
    )
    (net (code "88") (name "Net-(U11-~{FAULT})") (class "Default")
      (node (ref "R31") (pin "1") (pinfunction "1_1") (pintype "passive"))
      (node (ref "U11") (pin "4") (pinfunction "~{FAULT}_4") (pintype "bidirectional"))
    )
    (net (code "89") (name "PGOOD") (class "Default")
      (node (ref "R18") (pin "2") (pinfunction "2_2") (pintype "bidirectional"))
      (node (ref "U10") (pin "14") (pinfunction "PGOOD_14") (pintype "bidirectional"))
    )
    (net (code "90") (name "PMID") (class "Default")
      (node (ref "U1") (pin "47") (pinfunction "PMID_47") (pintype "bidirectional"))
    )
    (net (code "91") (name "R") (class "Default")
      (node (ref "R13") (pin "1") (pinfunction "1_1") (pintype "bidirectional"))
      (node (ref "U1") (pin "30") (pinfunction "RED_30") (pintype "bidirectional"))
    )
    (net (code "92") (name "RESET") (class "Default")
      (node (ref "BUTTON1") (pin "3") (pinfunction "P$3_3") (pintype "bidirectional"))
      (node (ref "BUTTON1") (pin "4") (pinfunction "P$4_4") (pintype "bidirectional"))
      (node (ref "DEBUG") (pin "10") (pinfunction "10_10") (pintype "bidirectional"))
      (node (ref "TP11") (pin "TP") (pinfunction "TP_TP") (pintype "input"))
      (node (ref "U1") (pin "33") (pinfunction "RESET_33") (pintype "bidirectional"))
    )
    (net (code "93") (name "RIND") (class "Default")
      (node (ref "R24") (pin "2") (pinfunction "2_2") (pintype "bidirectional"))
      (node (ref "U10") (pin "8") (pinfunction "RIND_8") (pintype "bidirectional"))
    )
    (net (code "94") (name "RTC_BAT") (class "Default")
      (node (ref "C1") (pin "1") (pinfunction "1_1") (pintype "bidirectional"))
      (node (ref "R3") (pin "1") (pinfunction "1_1") (pintype "passive"))
      (node (ref "U1") (pin "73") (pinfunction "RTC_BAT_73") (pintype "bidirectional"))
    )
    (net (code "95") (name "RTC_BTN") (class "Default")
      (node (ref "R2") (pin "1") (pinfunction "1_1") (pintype "bidirectional"))
      (node (ref "U1") (pin "74") (pinfunction "RTC_BTN_74") (pintype "bidirectional"))
    )
    (net (code "96") (name "SAW_IN") (class "Default")
      (node (ref "C19") (pin "1") (pinfunction "1_1") (pintype "bidirectional"))
      (node (ref "C22") (pin "1") (pinfunction "1_1") (pintype "bidirectional"))
      (node (ref "U7") (pin "1") (pinfunction "INPUT_1") (pintype "input"))
    )
    (net (code "97") (name "SCK0") (class "Default")
      (node (ref "U1") (pin "39") (pinfunction "A6_39") (pintype "bidirectional"))
      (node (ref "U9") (pin "6") (pinfunction "SCK_6") (pintype "input"))
    )
    (net (code "98") (name "SHIELD") (class "Default")
      (node (ref "C17") (pin "1") (pinfunction "1_1") (pintype "bidirectional"))
      (node (ref "J2") (pin "S1") (pinfunction "SHIELD_S1") (pintype "passive"))
      (node (ref "J2") (pin "S2") (pinfunction "SHIELD_S2") (pintype "passive"))
      (node (ref "J2") (pin "S3") (pinfunction "SHIELD_S3") (pintype "passive"))
      (node (ref "J2") (pin "S4") (pinfunction "SHIELD_S4") (pintype "passive"))
      (node (ref "L13") (pin "1") (pinfunction "1_1") (pintype "bidirectional"))
      (node (ref "R14") (pin "1") (pinfunction "1_1") (pintype "bidirectional"))
    )
    (net (code "99") (name "SIM_CLK") (class "Default")
      (node (ref "C14") (pin "2") (pinfunction "2_2") (pintype "bidirectional"))
      (node (ref "TP29") (pin "TP") (pinfunction "TP_TP") (pintype "input"))
      (node (ref "U1") (pin "104") (pinfunction "RESV_104") (pintype "bidirectional"))
    )
    (net (code "100") (name "SIM_DATA") (class "Default")
      (node (ref "C15") (pin "2") (pinfunction "2_2") (pintype "bidirectional"))
      (node (ref "R7") (pin "1") (pinfunction "1_1") (pintype "bidirectional"))
      (node (ref "TP31") (pin "TP") (pinfunction "TP_TP") (pintype "input"))
      (node (ref "U1") (pin "103") (pinfunction "RESV_103") (pintype "bidirectional"))
    )
    (net (code "101") (name "SIM_RST") (class "Default")
      (node (ref "C13") (pin "2") (pinfunction "2_2") (pintype "bidirectional"))
      (node (ref "TP28") (pin "TP") (pinfunction "TP_TP") (pintype "input"))
      (node (ref "U1") (pin "102") (pinfunction "RESV_102") (pintype "bidirectional"))
    )
    (net (code "102") (name "SIM_VCC") (class "Default")
      (node (ref "C16") (pin "1") (pinfunction "1_1") (pintype "bidirectional"))
      (node (ref "R7") (pin "2") (pinfunction "2_2") (pintype "bidirectional"))
      (node (ref "TP27") (pin "TP") (pinfunction "TP_TP") (pintype "input"))
      (node (ref "U1") (pin "101") (pinfunction "RESV_101") (pintype "bidirectional"))
    )
    (net (code "103") (name "SOM9") (class "Default")
      (node (ref "U1") (pin "9") (pinfunction "NC_9") (pintype "bidirectional"))
    )
    (net (code "104") (name "SOM18") (class "Default")
      (node (ref "U1") (pin "18") (pinfunction "NC_18") (pintype "bidirectional"))
    )
    (net (code "105") (name "SOM19") (class "Default")
      (node (ref "U1") (pin "19") (pinfunction "NC_19") (pintype "bidirectional"))
    )
    (net (code "106") (name "SOM20") (class "Default")
      (node (ref "U1") (pin "20") (pinfunction "NC_20") (pintype "bidirectional"))
    )
    (net (code "107") (name "SOM21") (class "Default")
      (node (ref "U1") (pin "21") (pinfunction "NC_21") (pintype "bidirectional"))
    )
    (net (code "108") (name "SOM34") (class "Default")
      (node (ref "U1") (pin "34") (pinfunction "NC_34") (pintype "bidirectional"))
    )
    (net (code "109") (name "SOM35") (class "Default")
      (node (ref "U1") (pin "35") (pinfunction "NC_35") (pintype "bidirectional"))
    )
    (net (code "110") (name "SOM36") (class "Default")
      (node (ref "U1") (pin "36") (pinfunction "NC_36") (pintype "bidirectional"))
    )
    (net (code "111") (name "SOM37") (class "Default")
      (node (ref "U1") (pin "37") (pinfunction "NC_37") (pintype "bidirectional"))
    )
    (net (code "112") (name "SOM44") (class "Default")
      (node (ref "U1") (pin "44") (pinfunction "NC_44") (pintype "bidirectional"))
    )
    (net (code "113") (name "SOM59") (class "Default")
      (node (ref "U1") (pin "59") (pinfunction "NC_59") (pintype "bidirectional"))
    )
    (net (code "114") (name "SOM60") (class "Default")
      (node (ref "U1") (pin "60") (pinfunction "NC_60") (pintype "bidirectional"))
    )
    (net (code "115") (name "SOM61") (class "Default")
      (node (ref "U1") (pin "61") (pinfunction "NC_61") (pintype "bidirectional"))
    )
    (net (code "116") (name "SOM62") (class "Default")
      (node (ref "U1") (pin "62") (pinfunction "NC_62") (pintype "bidirectional"))
    )
    (net (code "117") (name "SOM76") (class "Default")
      (node (ref "U1") (pin "76") (pinfunction "NC_76") (pintype "bidirectional"))
    )
    (net (code "118") (name "SOM77") (class "Default")
      (node (ref "U1") (pin "77") (pinfunction "NC_77") (pintype "bidirectional"))
    )
    (net (code "119") (name "SOM78") (class "Default")
      (node (ref "U1") (pin "78") (pinfunction "NC_78") (pintype "bidirectional"))
    )
    (net (code "120") (name "SOM79") (class "Default")
      (node (ref "U1") (pin "79") (pinfunction "NC_79") (pintype "bidirectional"))
    )
    (net (code "121") (name "SOM80") (class "Default")
      (node (ref "U1") (pin "80") (pinfunction "NC_80") (pintype "bidirectional"))
    )
    (net (code "122") (name "SOM81") (class "Default")
      (node (ref "U1") (pin "81") (pinfunction "NC_81") (pintype "bidirectional"))
    )
    (net (code "123") (name "SOM82") (class "Default")
      (node (ref "U1") (pin "82") (pinfunction "NC_82") (pintype "bidirectional"))
    )
    (net (code "124") (name "SS") (class "Default")
      (node (ref "C35") (pin "1") (pinfunction "1_1") (pintype "bidirectional"))
      (node (ref "R19") (pin "1") (pinfunction "1_1") (pintype "bidirectional"))
      (node (ref "U10") (pin "15") (pinfunction "SS_15") (pintype "bidirectional"))
    )
    (net (code "125") (name "STAT") (class "Default")
      (node (ref "LED1") (pin "1") (pinfunction "K_1") (pintype "bidirectional"))
      (node (ref "U1") (pin "50") (pinfunction "STAT_50") (pintype "bidirectional"))
    )
    (net (code "126") (name "SWDCLK") (class "Default")
      (node (ref "DEBUG") (pin "4") (pinfunction "4_4") (pintype "bidirectional"))
      (node (ref "TP13") (pin "TP") (pinfunction "TP_TP") (pintype "input"))
      (node (ref "U1") (pin "23") (pinfunction "SWDCLK_23") (pintype "bidirectional"))
    )
    (net (code "127") (name "SWDIO") (class "Default")
      (node (ref "DEBUG") (pin "2") (pinfunction "2_2") (pintype "bidirectional"))
      (node (ref "TP15") (pin "TP") (pinfunction "TP_TP") (pintype "input"))
      (node (ref "U1") (pin "22") (pinfunction "SWDIO_22") (pintype "bidirectional"))
    )
    (net (code "128") (name "SWO") (class "Default")
      (node (ref "DEBUG") (pin "6") (pinfunction "6_6") (pintype "bidirectional"))
      (node (ref "TP12") (pin "TP") (pinfunction "TP_TP") (pintype "input"))
      (node (ref "U1") (pin "24") (pinfunction "SWO_24") (pintype "bidirectional"))
    )
    (net (code "129") (name "TS") (class "Default")
      (node (ref "R50") (pin "1") (pinfunction "1_1") (pintype "bidirectional"))
      (node (ref "U1") (pin "46") (pinfunction "TS_46") (pintype "bidirectional"))
    )
    (net (code "130") (name "UVBUS") (class "Default")
      (node (ref "C45") (pin "1") (pinfunction "1_1") (pintype "bidirectional"))
      (node (ref "R67") (pin "1") (pinfunction "1_1") (pintype "bidirectional"))
      (node (ref "S1") (pin "A1") (pinfunction "A1_A1") (pintype "passive"))
      (node (ref "TP17") (pin "TP") (pinfunction "TP_TP") (pintype "input"))
      (node (ref "TP33") (pin "TP") (pinfunction "TP_TP") (pintype "input"))
      (node (ref "U12") (pin "P$3") (pinfunction "CE_P$3") (pintype "bidirectional"))
      (node (ref "U12") (pin "P$4") (pinfunction "VIN_P$4") (pintype "bidirectional"))
    )
    (net (code "131") (name "VBUS_SOM") (class "Default")
      (node (ref "C21") (pin "1") (pinfunction "1_1") (pintype "bidirectional"))
      (node (ref "C26") (pin "2") (pinfunction "2_2") (pintype "bidirectional"))
      (node (ref "C7") (pin "1") (pinfunction "1_1") (pintype "bidirectional"))
      (node (ref "F1") (pin "2") (pinfunction "2_2") (pintype "bidirectional"))
      (node (ref "S1") (pin "1") (pinfunction "1_1") (pintype "passive"))
      (node (ref "U1") (pin "51") (pinfunction "VBUS_51") (pintype "bidirectional"))
    )
    (net (code "132") (name "VIN") (class "Default")
      (node (ref "C50") (pin "1") (pinfunction "1_1") (pintype "bidirectional"))
      (node (ref "D5") (pin "A") (pinfunction "A_A") (pintype "passive"))
      (node (ref "J1") (pin "1") (pinfunction "1_1") (pintype "passive"))
      (node (ref "TP23") (pin "TP") (pinfunction "TP_TP") (pintype "input"))
      (node (ref "TP43") (pin "TP") (pinfunction "TP_TP") (pintype "input"))
      (node (ref "TP45") (pin "TP") (pinfunction "TP_TP") (pintype "input"))
    )
    (net (code "133") (name "VIN1") (class "Default")
      (node (ref "C38") (pin "1") (pinfunction "1_1") (pintype "passive"))
      (node (ref "D3") (pin "C") (pinfunction "C_C") (pintype "passive"))
      (node (ref "D5") (pin "C") (pinfunction "C_C") (pintype "passive"))
      (node (ref "L6") (pin "1") (pinfunction "1_1") (pintype "passive"))
      (node (ref "R30") (pin "1") (pinfunction "1_1") (pintype "passive"))
    )
    (net (code "134") (name "VIN_SOM") (class "Default")
      (node (ref "C30") (pin "1") (pinfunction "1_1") (pintype "bidirectional"))
      (node (ref "C32") (pin "1") (pinfunction "1_1") (pintype "bidirectional"))
      (node (ref "C6") (pin "1") (pinfunction "1_1") (pintype "bidirectional"))
      (node (ref "C8") (pin "1") (pinfunction "1_1") (pintype "bidirectional"))
      (node (ref "L5") (pin "2") (pinfunction "2_2") (pintype "passive"))
      (node (ref "TP10") (pin "TP") (pinfunction "TP_TP") (pintype "input"))
      (node (ref "U1") (pin "49") (pinfunction "VIN_49") (pintype "bidirectional"))
    )
    (net (code "135") (name "VVBUS") (class "Default")
      (node (ref "D10") (pin "1") (pinfunction "1_1") (pintype "passive"))
      (node (ref "F1") (pin "1") (pinfunction "1_1") (pintype "bidirectional"))
      (node (ref "J2") (pin "A4") (pinfunction "VBUSA1_A4") (pintype "power_in"))
      (node (ref "J2") (pin "A9") (pinfunction "VBUSA2_A9") (pintype "power_in"))
      (node (ref "J2") (pin "B4") (pinfunction "VBUSB1_B4") (pintype "power_in"))
      (node (ref "J2") (pin "B9") (pinfunction "VBUSB2_B9") (pintype "power_in"))
    )
    (net (code "136") (name "WIFI_BOOT") (class "Default")
      (node (ref "TP3") (pin "TP") (pinfunction "TP_TP") (pintype "input"))
      (node (ref "U1") (pin "12") (pinfunction "WIFI_BOOT_12") (pintype "bidirectional"))
    )
    (net (code "137") (name "WIFI_EN") (class "Default")
      (node (ref "TP4") (pin "TP") (pinfunction "TP_TP") (pintype "input"))
      (node (ref "U1") (pin "11") (pinfunction "WIFI_EN_11") (pintype "bidirectional"))
    )
    (net (code "138") (name "WIFI_RXD") (class "Default")
      (node (ref "TP1") (pin "TP") (pinfunction "TP_TP") (pintype "input"))
      (node (ref "U1") (pin "14") (pinfunction "WIFI_RXD_14") (pintype "bidirectional"))
    )
    (net (code "139") (name "WIFI_TXD") (class "Default")
      (node (ref "TP2") (pin "TP") (pinfunction "TP_TP") (pintype "input"))
      (node (ref "U1") (pin "13") (pinfunction "WIFI_TXD_13") (pintype "bidirectional"))
    )
    (net (code "140") (name "Y1") (class "Default")
      (node (ref "TP42") (pin "TP") (pinfunction "TP_TP") (pintype "input"))
      (node (ref "U1") (pin "100") (pinfunction "RESV_100") (pintype "bidirectional"))
    )
    (net (code "141") (name "Y5") (class "Default")
      (node (ref "TP41") (pin "TP") (pinfunction "TP_TP") (pintype "input"))
      (node (ref "U1") (pin "99") (pinfunction "RESV_99") (pintype "bidirectional"))
    )
    (net (code "142") (name "unconnected-(DEBUG-Pad7)") (class "Default")
      (node (ref "DEBUG") (pin "7") (pinfunction "7_7") (pintype "bidirectional"))
    )
    (net (code "143") (name "unconnected-(DEBUG-Pad8)") (class "Default")
      (node (ref "DEBUG") (pin "8") (pinfunction "8_8") (pintype "bidirectional"))
    )
    (net (code "144") (name "unconnected-(ESD1-C-Pad3)") (class "Default")
      (node (ref "ESD1") (pin "3") (pinfunction "C_3") (pintype "passive"))
    )
    (net (code "145") (name "unconnected-(ESD2-C-Pad3)") (class "Default")
      (node (ref "ESD2") (pin "3") (pinfunction "C_3") (pintype "passive"))
    )
    (net (code "146") (name "unconnected-(J2-RX1+-PadB11)") (class "Default")
      (node (ref "J2") (pin "B11") (pinfunction "RX1+_B11") (pintype "bidirectional"))
    )
    (net (code "147") (name "unconnected-(J2-RX1--PadB10)") (class "Default")
      (node (ref "J2") (pin "B10") (pinfunction "RX1-_B10") (pintype "bidirectional"))
    )
    (net (code "148") (name "unconnected-(J2-RX2+-PadA11)") (class "Default")
      (node (ref "J2") (pin "A11") (pinfunction "RX2+_A11") (pintype "bidirectional"))
    )
    (net (code "149") (name "unconnected-(J2-RX2--PadA10)") (class "Default")
      (node (ref "J2") (pin "A10") (pinfunction "RX2-_A10") (pintype "bidirectional"))
    )
    (net (code "150") (name "unconnected-(J2-SBU1-PadA8)") (class "Default")
      (node (ref "J2") (pin "A8") (pinfunction "SBU1_A8") (pintype "bidirectional"))
    )
    (net (code "151") (name "unconnected-(J2-SBU2-PadB8)") (class "Default")
      (node (ref "J2") (pin "B8") (pinfunction "SBU2_B8") (pintype "bidirectional"))
    )
    (net (code "152") (name "unconnected-(J2-TX1+-PadA2)") (class "Default")
      (node (ref "J2") (pin "A2") (pinfunction "TX1+_A2") (pintype "bidirectional"))
    )
    (net (code "153") (name "unconnected-(J2-TX1--PadA3)") (class "Default")
      (node (ref "J2") (pin "A3") (pinfunction "TX1-_A3") (pintype "bidirectional"))
    )
    (net (code "154") (name "unconnected-(J2-TX2+-PadB2)") (class "Default")
      (node (ref "J2") (pin "B2") (pinfunction "TX2+_B2") (pintype "bidirectional"))
    )
    (net (code "155") (name "unconnected-(J2-TX2--PadB3)") (class "Default")
      (node (ref "J2") (pin "B3") (pinfunction "TX2-_B3") (pintype "bidirectional"))
    )
    (net (code "156") (name "unconnected-(U10-ICTRL-Pad16)") (class "Default")
      (node (ref "U10") (pin "16") (pinfunction "ICTRL_16") (pintype "bidirectional"))
    )
    (net (code "157") (name "unconnected-(U10-OVLO-Pad7)") (class "Default")
      (node (ref "U10") (pin "7") (pinfunction "OVLO_7") (pintype "bidirectional"))
    )
    (net (code "158") (name "unconnected-(U10-VPRG1-Pad18)") (class "Default")
      (node (ref "U10") (pin "18") (pinfunction "VPRG1_18") (pintype "bidirectional"))
    )
    (net (code "159") (name "{slash}FRAM_CS") (class "Default")
      (node (ref "R32") (pin "1") (pinfunction "1_1") (pintype "bidirectional"))
      (node (ref "U1") (pin "38") (pinfunction "A7_38") (pintype "bidirectional"))
      (node (ref "U9") (pin "1") (pinfunction "~{CS}_1") (pintype "output"))
    )
    (net (code "160") (name "~{FRAM_HOLD}") (class "Default")
      (node (ref "R34") (pin "1") (pinfunction "1_1") (pintype "bidirectional"))
      (node (ref "U9") (pin "7") (pinfunction "~{HOLD}_7") (pintype "output"))
    )
  )
)
